# cyberspace-1-mainboard.net
KiCad netlist of a schematic drawn in EAGLE
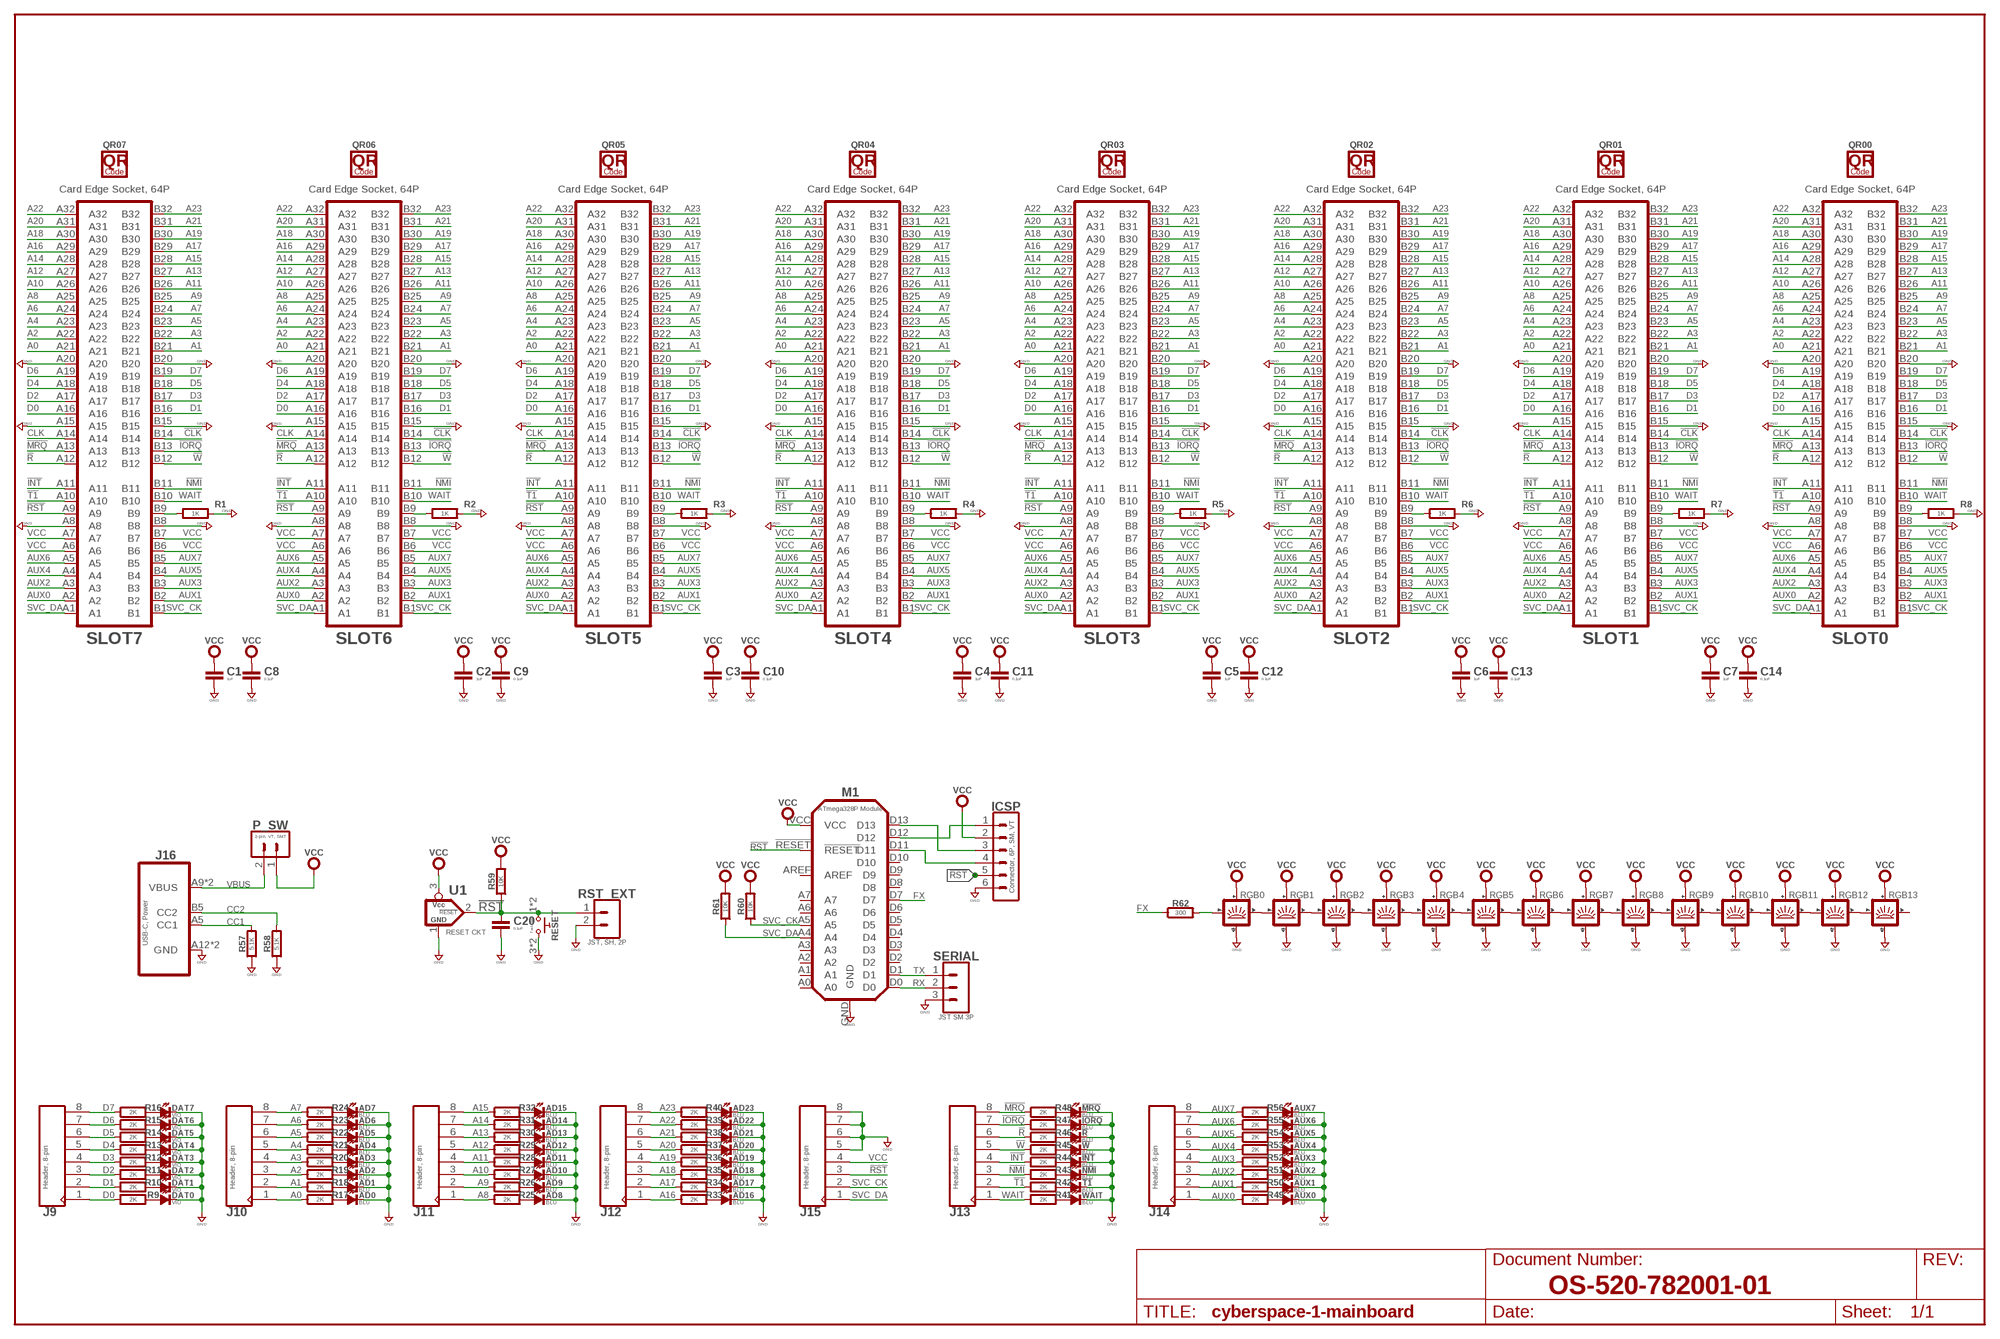
[diagram p0: schematic, sheet 1]

(export (version "E")
  (design (tool "Eeschema 10.0.6"))
  (components
    (comp (ref "!INT")
      (value "BLU")
      (footprint "eagle-import:SMD_0603")
      (libsource (lib "eagle-import") (part "SMT0603"))
    )
    (comp (ref "!IORQ")
      (value "BLU")
      (footprint "eagle-import:SMD_0603")
      (libsource (lib "eagle-import") (part "SMT0603"))
    )
    (comp (ref "!MRQ")
      (value "BLU")
      (footprint "eagle-import:SMD_0603")
      (libsource (lib "eagle-import") (part "SMT0603"))
    )
    (comp (ref "!NMI")
      (value "BLU")
      (footprint "eagle-import:SMD_0603")
      (libsource (lib "eagle-import") (part "SMT0603"))
    )
    (comp (ref "!R")
      (value "BLU")
      (footprint "eagle-import:SMD_0603")
      (libsource (lib "eagle-import") (part "SMT0603"))
    )
    (comp (ref "!T1")
      (value "BLU")
      (footprint "eagle-import:SMD_0603")
      (libsource (lib "eagle-import") (part "SMT0603"))
    )
    (comp (ref "!W")
      (value "BLU")
      (footprint "eagle-import:SMD_0603")
      (libsource (lib "eagle-import") (part "SMT0603"))
    )
    (comp (ref "AD0")
      (value "BLU")
      (footprint "eagle-import:SMD_0603")
      (libsource (lib "eagle-import") (part "SMT0603"))
    )
    (comp (ref "AD1")
      (value "BLU")
      (footprint "eagle-import:SMD_0603")
      (libsource (lib "eagle-import") (part "SMT0603"))
    )
    (comp (ref "AD2")
      (value "BLU")
      (footprint "eagle-import:SMD_0603")
      (libsource (lib "eagle-import") (part "SMT0603"))
    )
    (comp (ref "AD3")
      (value "BLU")
      (footprint "eagle-import:SMD_0603")
      (libsource (lib "eagle-import") (part "SMT0603"))
    )
    (comp (ref "AD4")
      (value "BLU")
      (footprint "eagle-import:SMD_0603")
      (libsource (lib "eagle-import") (part "SMT0603"))
    )
    (comp (ref "AD5")
      (value "BLU")
      (footprint "eagle-import:SMD_0603")
      (libsource (lib "eagle-import") (part "SMT0603"))
    )
    (comp (ref "AD6")
      (value "BLU")
      (footprint "eagle-import:SMD_0603")
      (libsource (lib "eagle-import") (part "SMT0603"))
    )
    (comp (ref "AD7")
      (value "BLU")
      (footprint "eagle-import:SMD_0603")
      (libsource (lib "eagle-import") (part "SMT0603"))
    )
    (comp (ref "AD8")
      (value "BLU")
      (footprint "eagle-import:SMD_0603")
      (libsource (lib "eagle-import") (part "SMT0603"))
    )
    (comp (ref "AD9")
      (value "BLU")
      (footprint "eagle-import:SMD_0603")
      (libsource (lib "eagle-import") (part "SMT0603"))
    )
    (comp (ref "AD10")
      (value "BLU")
      (footprint "eagle-import:SMD_0603")
      (libsource (lib "eagle-import") (part "SMT0603"))
    )
    (comp (ref "AD11")
      (value "BLU")
      (footprint "eagle-import:SMD_0603")
      (libsource (lib "eagle-import") (part "SMT0603"))
    )
    (comp (ref "AD12")
      (value "BLU")
      (footprint "eagle-import:SMD_0603")
      (libsource (lib "eagle-import") (part "SMT0603"))
    )
    (comp (ref "AD13")
      (value "BLU")
      (footprint "eagle-import:SMD_0603")
      (libsource (lib "eagle-import") (part "SMT0603"))
    )
    (comp (ref "AD14")
      (value "BLU")
      (footprint "eagle-import:SMD_0603")
      (libsource (lib "eagle-import") (part "SMT0603"))
    )
    (comp (ref "AD15")
      (value "BLU")
      (footprint "eagle-import:SMD_0603")
      (libsource (lib "eagle-import") (part "SMT0603"))
    )
    (comp (ref "AD16")
      (value "BLU")
      (footprint "eagle-import:SMD_0603")
      (libsource (lib "eagle-import") (part "SMT0603"))
    )
    (comp (ref "AD17")
      (value "BLU")
      (footprint "eagle-import:SMD_0603")
      (libsource (lib "eagle-import") (part "SMT0603"))
    )
    (comp (ref "AD18")
      (value "BLU")
      (footprint "eagle-import:SMD_0603")
      (libsource (lib "eagle-import") (part "SMT0603"))
    )
    (comp (ref "AD19")
      (value "BLU")
      (footprint "eagle-import:SMD_0603")
      (libsource (lib "eagle-import") (part "SMT0603"))
    )
    (comp (ref "AD20")
      (value "BLU")
      (footprint "eagle-import:SMD_0603")
      (libsource (lib "eagle-import") (part "SMT0603"))
    )
    (comp (ref "AD21")
      (value "BLU")
      (footprint "eagle-import:SMD_0603")
      (libsource (lib "eagle-import") (part "SMT0603"))
    )
    (comp (ref "AD22")
      (value "BLU")
      (footprint "eagle-import:SMD_0603")
      (libsource (lib "eagle-import") (part "SMT0603"))
    )
    (comp (ref "AD23")
      (value "BLU")
      (footprint "eagle-import:SMD_0603")
      (libsource (lib "eagle-import") (part "SMT0603"))
    )
    (comp (ref "AUX0")
      (value "BLU")
      (footprint "eagle-import:SMD_0603")
      (libsource (lib "eagle-import") (part "SMT0603"))
    )
    (comp (ref "AUX1")
      (value "BLU")
      (footprint "eagle-import:SMD_0603")
      (libsource (lib "eagle-import") (part "SMT0603"))
    )
    (comp (ref "AUX2")
      (value "BLU")
      (footprint "eagle-import:SMD_0603")
      (libsource (lib "eagle-import") (part "SMT0603"))
    )
    (comp (ref "AUX3")
      (value "BLU")
      (footprint "eagle-import:SMD_0603")
      (libsource (lib "eagle-import") (part "SMT0603"))
    )
    (comp (ref "AUX4")
      (value "BLU")
      (footprint "eagle-import:SMD_0603")
      (libsource (lib "eagle-import") (part "SMT0603"))
    )
    (comp (ref "AUX5")
      (value "BLU")
      (footprint "eagle-import:SMD_0603")
      (libsource (lib "eagle-import") (part "SMT0603"))
    )
    (comp (ref "AUX6")
      (value "BLU")
      (footprint "eagle-import:SMD_0603")
      (libsource (lib "eagle-import") (part "SMT0603"))
    )
    (comp (ref "AUX7")
      (value "BLU")
      (footprint "eagle-import:SMD_0603")
      (libsource (lib "eagle-import") (part "SMT0603"))
    )
    (comp (ref "C1")
      (value "1uF")
      (footprint "eagle-import:0603-CAP")
      (libsource (lib "eagle-import") (part "CAPACITOR0603"))
    )
    (comp (ref "C2")
      (value "1uF")
      (footprint "eagle-import:0603-CAP")
      (libsource (lib "eagle-import") (part "CAPACITOR0603"))
    )
    (comp (ref "C3")
      (value "1uF")
      (footprint "eagle-import:0603-CAP")
      (libsource (lib "eagle-import") (part "CAPACITOR0603"))
    )
    (comp (ref "C4")
      (value "1uF")
      (footprint "eagle-import:0603-CAP")
      (libsource (lib "eagle-import") (part "CAPACITOR0603"))
    )
    (comp (ref "C5")
      (value "1uF")
      (footprint "eagle-import:0603-CAP")
      (libsource (lib "eagle-import") (part "CAPACITOR0603"))
    )
    (comp (ref "C6")
      (value "1uF")
      (footprint "eagle-import:0603-CAP")
      (libsource (lib "eagle-import") (part "CAPACITOR0603"))
    )
    (comp (ref "C7")
      (value "1uF")
      (footprint "eagle-import:0603-CAP")
      (libsource (lib "eagle-import") (part "CAPACITOR0603"))
    )
    (comp (ref "C8")
      (value "0.1uF")
      (footprint "eagle-import:0603-CAP")
      (libsource (lib "eagle-import") (part "CAPACITOR0603"))
    )
    (comp (ref "C9")
      (value "0.1uF")
      (footprint "eagle-import:0603-CAP")
      (libsource (lib "eagle-import") (part "CAPACITOR0603"))
    )
    (comp (ref "C10")
      (value "0.1uF")
      (footprint "eagle-import:0603-CAP")
      (libsource (lib "eagle-import") (part "CAPACITOR0603"))
    )
    (comp (ref "C11")
      (value "0.1uF")
      (footprint "eagle-import:0603-CAP")
      (libsource (lib "eagle-import") (part "CAPACITOR0603"))
    )
    (comp (ref "C12")
      (value "0.1uF")
      (footprint "eagle-import:0603-CAP")
      (libsource (lib "eagle-import") (part "CAPACITOR0603"))
    )
    (comp (ref "C13")
      (value "0.1uF")
      (footprint "eagle-import:0603-CAP")
      (libsource (lib "eagle-import") (part "CAPACITOR0603"))
    )
    (comp (ref "C14")
      (value "0.1uF")
      (footprint "eagle-import:0603-CAP")
      (libsource (lib "eagle-import") (part "CAPACITOR0603"))
    )
    (comp (ref "C20")
      (value "0.1uF")
      (footprint "eagle-import:0603-CAP")
      (libsource (lib "eagle-import") (part "CAPACITOR0603"))
    )
    (comp (ref "DAT0")
      (value "VIO")
      (footprint "eagle-import:SMD_0603")
      (libsource (lib "eagle-import") (part "SMT0603"))
    )
    (comp (ref "DAT1")
      (value "VIO")
      (footprint "eagle-import:SMD_0603")
      (libsource (lib "eagle-import") (part "SMT0603"))
    )
    (comp (ref "DAT2")
      (value "VIO")
      (footprint "eagle-import:SMD_0603")
      (libsource (lib "eagle-import") (part "SMT0603"))
    )
    (comp (ref "DAT3")
      (value "VIO")
      (footprint "eagle-import:SMD_0603")
      (libsource (lib "eagle-import") (part "SMT0603"))
    )
    (comp (ref "DAT4")
      (value "VIO")
      (footprint "eagle-import:SMD_0603")
      (libsource (lib "eagle-import") (part "SMT0603"))
    )
    (comp (ref "DAT5")
      (value "VIO")
      (footprint "eagle-import:SMD_0603")
      (libsource (lib "eagle-import") (part "SMT0603"))
    )
    (comp (ref "DAT6")
      (value "VIO")
      (footprint "eagle-import:SMD_0603")
      (libsource (lib "eagle-import") (part "SMT0603"))
    )
    (comp (ref "DAT7")
      (value "VIO")
      (footprint "eagle-import:SMD_0603")
      (libsource (lib "eagle-import") (part "SMT0603"))
    )
    (comp (ref "ICSP")
      (value "Connector, 6P, SM, VT")
      (footprint "eagle-import:BM06B-SRSS-TB")
      (fields (field (name "MFR") "JST") (field (name "MPN") "BM06-SRSS-TB"))
      (libsource (lib "eagle-import") (part "06P-SM-VT-SMT"))
    )
    (comp (ref "J9")
      (value "Header, 8-pin")
      (footprint "eagle-import:MA08X1-VT-THD")
      (libsource (lib "eagle-import") (part "CON_08X1-VT-THD"))
    )
    (comp (ref "J10")
      (value "Header, 8-pin")
      (footprint "eagle-import:MA08X1-VT-THD")
      (libsource (lib "eagle-import") (part "CON_08X1-VT-THD"))
    )
    (comp (ref "J11")
      (value "Header, 8-pin")
      (footprint "eagle-import:MA08X1-VT-THD")
      (libsource (lib "eagle-import") (part "CON_08X1-VT-THD"))
    )
    (comp (ref "J12")
      (value "Header, 8-pin")
      (footprint "eagle-import:MA08X1-VT-THD")
      (libsource (lib "eagle-import") (part "CON_08X1-VT-THD"))
    )
    (comp (ref "J13")
      (value "Header, 8-pin")
      (footprint "eagle-import:MA08X1-VT-THD")
      (libsource (lib "eagle-import") (part "CON_08X1-VT-THD"))
    )
    (comp (ref "J14")
      (value "Header, 8-pin")
      (footprint "eagle-import:MA08X1-VT-THD")
      (libsource (lib "eagle-import") (part "CON_08X1-VT-THD"))
    )
    (comp (ref "J15")
      (value "Header, 8-pin")
      (footprint "eagle-import:MA08X1-VT-THD")
      (libsource (lib "eagle-import") (part "CON_08X1-VT-THD"))
    )
    (comp (ref "J16")
      (value "USB-C, Power")
      (footprint "eagle-import:GCT-USB4125")
      (fields (field (name "MFR") "GCT") (field (name "MPN") "USB4125"))
      (libsource (lib "eagle-import") (part "USB-C-PWRSMT-HORIZ"))
    )
    (comp (ref "M1")
      (value "ATmega328P Module")
      (footprint "eagle-import:0119A")
      (fields (field (name "MFR") "Circuit Monkey") (field (name "MPN") "0119A"))
      (libsource (lib "eagle-import") (part "0119REV-A"))
    )
    (comp (ref "P_SW")
      (value "2-pin, VT, SMT")
      (footprint "eagle-import:B2B-PH-SM4")
      (fields (field (name "MFR") "JST") (field (name "MPN") "B2B-PH-SM4"))
      (libsource (lib "eagle-import") (part "02PVT-SMT"))
    )
    (comp (ref "QR00")
      (value "QR_CODE-00-7MM")
      (footprint "eagle-import:QR-7MM-00")
      (libsource (lib "eagle-import") (part "QR_CODE-00-7MM"))
    )
    (comp (ref "QR01")
      (value "QR_CODE-01-7MM")
      (footprint "eagle-import:QR-7MM-01")
      (libsource (lib "eagle-import") (part "QR_CODE-01-7MM"))
    )
    (comp (ref "QR02")
      (value "QR_CODE-02-7MM")
      (footprint "eagle-import:QR-7MM-02")
      (libsource (lib "eagle-import") (part "QR_CODE-02-7MM"))
    )
    (comp (ref "QR03")
      (value "QR_CODE-03-7MM")
      (footprint "eagle-import:QR-7MM-03")
      (libsource (lib "eagle-import") (part "QR_CODE-03-7MM"))
    )
    (comp (ref "QR04")
      (value "QR_CODE-04-7MM")
      (footprint "eagle-import:QR-7MM-04")
      (libsource (lib "eagle-import") (part "QR_CODE-04-7MM"))
    )
    (comp (ref "QR05")
      (value "QR_CODE-05-7MM")
      (footprint "eagle-import:QR-7MM-05")
      (libsource (lib "eagle-import") (part "QR_CODE-05-7MM"))
    )
    (comp (ref "QR06")
      (value "QR_CODE-06-7MM")
      (footprint "eagle-import:QR-7MM-06")
      (libsource (lib "eagle-import") (part "QR_CODE-06-7MM"))
    )
    (comp (ref "QR07")
      (value "QR_CODE-07-7MM")
      (footprint "eagle-import:QR-7MM-07")
      (libsource (lib "eagle-import") (part "QR_CODE-07-7MM"))
    )
    (comp (ref "R1")
      (value "1K")
      (footprint "eagle-import:0603-RES")
      (libsource (lib "eagle-import") (part "RESISTOR0603"))
    )
    (comp (ref "R2")
      (value "1K")
      (footprint "eagle-import:0603-RES")
      (libsource (lib "eagle-import") (part "RESISTOR0603"))
    )
    (comp (ref "R3")
      (value "1K")
      (footprint "eagle-import:0603-RES")
      (libsource (lib "eagle-import") (part "RESISTOR0603"))
    )
    (comp (ref "R4")
      (value "1K")
      (footprint "eagle-import:0603-RES")
      (libsource (lib "eagle-import") (part "RESISTOR0603"))
    )
    (comp (ref "R5")
      (value "1K")
      (footprint "eagle-import:0603-RES")
      (libsource (lib "eagle-import") (part "RESISTOR0603"))
    )
    (comp (ref "R6")
      (value "1K")
      (footprint "eagle-import:0603-RES")
      (libsource (lib "eagle-import") (part "RESISTOR0603"))
    )
    (comp (ref "R7")
      (value "1K")
      (footprint "eagle-import:0603-RES")
      (libsource (lib "eagle-import") (part "RESISTOR0603"))
    )
    (comp (ref "R8")
      (value "1K")
      (footprint "eagle-import:0603-RES")
      (libsource (lib "eagle-import") (part "RESISTOR0603"))
    )
    (comp (ref "R9")
      (value "2K")
      (footprint "eagle-import:0603-RES")
      (libsource (lib "eagle-import") (part "RESISTOR0603"))
    )
    (comp (ref "R10")
      (value "2K")
      (footprint "eagle-import:0603-RES")
      (libsource (lib "eagle-import") (part "RESISTOR0603"))
    )
    (comp (ref "R11")
      (value "2K")
      (footprint "eagle-import:0603-RES")
      (libsource (lib "eagle-import") (part "RESISTOR0603"))
    )
    (comp (ref "R12")
      (value "2K")
      (footprint "eagle-import:0603-RES")
      (libsource (lib "eagle-import") (part "RESISTOR0603"))
    )
    (comp (ref "R13")
      (value "2K")
      (footprint "eagle-import:0603-RES")
      (libsource (lib "eagle-import") (part "RESISTOR0603"))
    )
    (comp (ref "R14")
      (value "2K")
      (footprint "eagle-import:0603-RES")
      (libsource (lib "eagle-import") (part "RESISTOR0603"))
    )
    (comp (ref "R15")
      (value "2K")
      (footprint "eagle-import:0603-RES")
      (libsource (lib "eagle-import") (part "RESISTOR0603"))
    )
    (comp (ref "R16")
      (value "2K")
      (footprint "eagle-import:0603-RES")
      (libsource (lib "eagle-import") (part "RESISTOR0603"))
    )
    (comp (ref "R17")
      (value "2K")
      (footprint "eagle-import:0603-RES")
      (libsource (lib "eagle-import") (part "RESISTOR0603"))
    )
    (comp (ref "R18")
      (value "2K")
      (footprint "eagle-import:0603-RES")
      (libsource (lib "eagle-import") (part "RESISTOR0603"))
    )
    (comp (ref "R19")
      (value "2K")
      (footprint "eagle-import:0603-RES")
      (libsource (lib "eagle-import") (part "RESISTOR0603"))
    )
    (comp (ref "R20")
      (value "2K")
      (footprint "eagle-import:0603-RES")
      (libsource (lib "eagle-import") (part "RESISTOR0603"))
    )
    (comp (ref "R21")
      (value "2K")
      (footprint "eagle-import:0603-RES")
      (libsource (lib "eagle-import") (part "RESISTOR0603"))
    )
    (comp (ref "R22")
      (value "2K")
      (footprint "eagle-import:0603-RES")
      (libsource (lib "eagle-import") (part "RESISTOR0603"))
    )
    (comp (ref "R23")
      (value "2K")
      (footprint "eagle-import:0603-RES")
      (libsource (lib "eagle-import") (part "RESISTOR0603"))
    )
    (comp (ref "R24")
      (value "2K")
      (footprint "eagle-import:0603-RES")
      (libsource (lib "eagle-import") (part "RESISTOR0603"))
    )
    (comp (ref "R25")
      (value "2K")
      (footprint "eagle-import:0603-RES")
      (libsource (lib "eagle-import") (part "RESISTOR0603"))
    )
    (comp (ref "R26")
      (value "2K")
      (footprint "eagle-import:0603-RES")
      (libsource (lib "eagle-import") (part "RESISTOR0603"))
    )
    (comp (ref "R27")
      (value "2K")
      (footprint "eagle-import:0603-RES")
      (libsource (lib "eagle-import") (part "RESISTOR0603"))
    )
    (comp (ref "R28")
      (value "2K")
      (footprint "eagle-import:0603-RES")
      (libsource (lib "eagle-import") (part "RESISTOR0603"))
    )
    (comp (ref "R29")
      (value "2K")
      (footprint "eagle-import:0603-RES")
      (libsource (lib "eagle-import") (part "RESISTOR0603"))
    )
    (comp (ref "R30")
      (value "2K")
      (footprint "eagle-import:0603-RES")
      (libsource (lib "eagle-import") (part "RESISTOR0603"))
    )
    (comp (ref "R31")
      (value "2K")
      (footprint "eagle-import:0603-RES")
      (libsource (lib "eagle-import") (part "RESISTOR0603"))
    )
    (comp (ref "R32")
      (value "2K")
      (footprint "eagle-import:0603-RES")
      (libsource (lib "eagle-import") (part "RESISTOR0603"))
    )
    (comp (ref "R33")
      (value "2K")
      (footprint "eagle-import:0603-RES")
      (libsource (lib "eagle-import") (part "RESISTOR0603"))
    )
    (comp (ref "R34")
      (value "2K")
      (footprint "eagle-import:0603-RES")
      (libsource (lib "eagle-import") (part "RESISTOR0603"))
    )
    (comp (ref "R35")
      (value "2K")
      (footprint "eagle-import:0603-RES")
      (libsource (lib "eagle-import") (part "RESISTOR0603"))
    )
    (comp (ref "R36")
      (value "2K")
      (footprint "eagle-import:0603-RES")
      (libsource (lib "eagle-import") (part "RESISTOR0603"))
    )
    (comp (ref "R37")
      (value "2K")
      (footprint "eagle-import:0603-RES")
      (libsource (lib "eagle-import") (part "RESISTOR0603"))
    )
    (comp (ref "R38")
      (value "2K")
      (footprint "eagle-import:0603-RES")
      (libsource (lib "eagle-import") (part "RESISTOR0603"))
    )
    (comp (ref "R39")
      (value "2K")
      (footprint "eagle-import:0603-RES")
      (libsource (lib "eagle-import") (part "RESISTOR0603"))
    )
    (comp (ref "R40")
      (value "2K")
      (footprint "eagle-import:0603-RES")
      (libsource (lib "eagle-import") (part "RESISTOR0603"))
    )
    (comp (ref "R41")
      (value "2K")
      (footprint "eagle-import:0603-RES")
      (libsource (lib "eagle-import") (part "RESISTOR0603"))
    )
    (comp (ref "R42")
      (value "2K")
      (footprint "eagle-import:0603-RES")
      (libsource (lib "eagle-import") (part "RESISTOR0603"))
    )
    (comp (ref "R43")
      (value "2K")
      (footprint "eagle-import:0603-RES")
      (libsource (lib "eagle-import") (part "RESISTOR0603"))
    )
    (comp (ref "R44")
      (value "2K")
      (footprint "eagle-import:0603-RES")
      (libsource (lib "eagle-import") (part "RESISTOR0603"))
    )
    (comp (ref "R45")
      (value "2K")
      (footprint "eagle-import:0603-RES")
      (libsource (lib "eagle-import") (part "RESISTOR0603"))
    )
    (comp (ref "R46")
      (value "2K")
      (footprint "eagle-import:0603-RES")
      (libsource (lib "eagle-import") (part "RESISTOR0603"))
    )
    (comp (ref "R47")
      (value "2K")
      (footprint "eagle-import:0603-RES")
      (libsource (lib "eagle-import") (part "RESISTOR0603"))
    )
    (comp (ref "R48")
      (value "2K")
      (footprint "eagle-import:0603-RES")
      (libsource (lib "eagle-import") (part "RESISTOR0603"))
    )
    (comp (ref "R49")
      (value "2K")
      (footprint "eagle-import:0603-RES")
      (libsource (lib "eagle-import") (part "RESISTOR0603"))
    )
    (comp (ref "R50")
      (value "2K")
      (footprint "eagle-import:0603-RES")
      (libsource (lib "eagle-import") (part "RESISTOR0603"))
    )
    (comp (ref "R51")
      (value "2K")
      (footprint "eagle-import:0603-RES")
      (libsource (lib "eagle-import") (part "RESISTOR0603"))
    )
    (comp (ref "R52")
      (value "2K")
      (footprint "eagle-import:0603-RES")
      (libsource (lib "eagle-import") (part "RESISTOR0603"))
    )
    (comp (ref "R53")
      (value "2K")
      (footprint "eagle-import:0603-RES")
      (libsource (lib "eagle-import") (part "RESISTOR0603"))
    )
    (comp (ref "R54")
      (value "2K")
      (footprint "eagle-import:0603-RES")
      (libsource (lib "eagle-import") (part "RESISTOR0603"))
    )
    (comp (ref "R55")
      (value "2K")
      (footprint "eagle-import:0603-RES")
      (libsource (lib "eagle-import") (part "RESISTOR0603"))
    )
    (comp (ref "R56")
      (value "2K")
      (footprint "eagle-import:0603-RES")
      (libsource (lib "eagle-import") (part "RESISTOR0603"))
    )
    (comp (ref "R57")
      (value "5.1K")
      (footprint "eagle-import:0603-RES")
      (libsource (lib "eagle-import") (part "RESISTOR0603"))
    )
    (comp (ref "R58")
      (value "5.1K")
      (footprint "eagle-import:0603-RES")
      (libsource (lib "eagle-import") (part "RESISTOR0603"))
    )
    (comp (ref "R59")
      (value "10K")
      (footprint "eagle-import:0603-RES")
      (libsource (lib "eagle-import") (part "RESISTOR0603"))
    )
    (comp (ref "R60")
      (value "10K")
      (footprint "eagle-import:0603-RES")
      (libsource (lib "eagle-import") (part "RESISTOR0603"))
    )
    (comp (ref "R61")
      (value "10K")
      (footprint "eagle-import:0603-RES")
      (libsource (lib "eagle-import") (part "RESISTOR0603"))
    )
    (comp (ref "R62")
      (value "300")
      (footprint "eagle-import:0603-RES")
      (libsource (lib "eagle-import") (part "RESISTOR0603"))
    )
    (comp (ref "RESET")
      (value "Tact. Sw.")
      (footprint "eagle-import:B3FS")
      (fields (field (name "MFR") "Omron") (field (name "MPN") "B3FS-10*"))
      (libsource (lib "eagle-import") (part "PUSHBTN-MOMB3FS"))
    )
    (comp (ref "RGB0")
      (value "SMART_LED4020-SIDE")
      (footprint "eagle-import:SMD_4020")
      (libsource (lib "eagle-import") (part "SMART_LED4020-SIDE"))
    )
    (comp (ref "RGB1")
      (value "SMART_LED4020-SIDE")
      (footprint "eagle-import:SMD_4020")
      (libsource (lib "eagle-import") (part "SMART_LED4020-SIDE"))
    )
    (comp (ref "RGB2")
      (value "SMART_LED4020-SIDE")
      (footprint "eagle-import:SMD_4020")
      (libsource (lib "eagle-import") (part "SMART_LED4020-SIDE"))
    )
    (comp (ref "RGB3")
      (value "SMART_LED4020-SIDE")
      (footprint "eagle-import:SMD_4020")
      (libsource (lib "eagle-import") (part "SMART_LED4020-SIDE"))
    )
    (comp (ref "RGB4")
      (value "SMART_LED4020-SIDE")
      (footprint "eagle-import:SMD_4020")
      (libsource (lib "eagle-import") (part "SMART_LED4020-SIDE"))
    )
    (comp (ref "RGB5")
      (value "SMART_LED4020-SIDE")
      (footprint "eagle-import:SMD_4020")
      (libsource (lib "eagle-import") (part "SMART_LED4020-SIDE"))
    )
    (comp (ref "RGB6")
      (value "SMART_LED4020-SIDE")
      (footprint "eagle-import:SMD_4020")
      (libsource (lib "eagle-import") (part "SMART_LED4020-SIDE"))
    )
    (comp (ref "RGB7")
      (value "SMART_LED4020-SIDE")
      (footprint "eagle-import:SMD_4020")
      (libsource (lib "eagle-import") (part "SMART_LED4020-SIDE"))
    )
    (comp (ref "RGB8")
      (value "SMART_LED4020-SIDE")
      (footprint "eagle-import:SMD_4020")
      (libsource (lib "eagle-import") (part "SMART_LED4020-SIDE"))
    )
    (comp (ref "RGB9")
      (value "SMART_LED4020-SIDE")
      (footprint "eagle-import:SMD_4020")
      (libsource (lib "eagle-import") (part "SMART_LED4020-SIDE"))
    )
    (comp (ref "RGB10")
      (value "SMART_LED4020-SIDE")
      (footprint "eagle-import:SMD_4020")
      (libsource (lib "eagle-import") (part "SMART_LED4020-SIDE"))
    )
    (comp (ref "RGB11")
      (value "SMART_LED4020-SIDE")
      (footprint "eagle-import:SMD_4020")
      (libsource (lib "eagle-import") (part "SMART_LED4020-SIDE"))
    )
    (comp (ref "RGB12")
      (value "SMART_LED4020-SIDE")
      (footprint "eagle-import:SMD_4020")
      (libsource (lib "eagle-import") (part "SMART_LED4020-SIDE"))
    )
    (comp (ref "RGB13")
      (value "SMART_LED4020-SIDE")
      (footprint "eagle-import:SMD_4020")
      (libsource (lib "eagle-import") (part "SMART_LED4020-SIDE"))
    )
    (comp (ref "RST_EXT")
      (value "JST, SH, 2P")
      (footprint "eagle-import:BM02B-SRSS-TB")
      (fields (field (name "MFR") "JST") (field (name "MPN") "BMB02B-SRSS-TB"))
      (libsource (lib "eagle-import") (part "02P-SM-VT-SMT"))
    )
    (comp (ref "SERIAL")
      (value "JST SM 3P")
      (footprint "eagle-import:BM03B-SRSS-TB")
      (fields (field (name "MFR") "JST") (field (name "MPN") "BM03B-SRSS-TB"))
      (libsource (lib "eagle-import") (part "03P-SM-VT-SMT"))
    )
    (comp (ref "SLOT0")
      (value "Card Edge Socket, 64P")
      (footprint "eagle-import:PCIE-64P-SOCKET")
      (fields (field (name "MFR") "FCI") (field (name "MPN") "10018784-xxx01"))
      (libsource (lib "eagle-import") (part "PCIE-64-SOCKET"))
    )
    (comp (ref "SLOT1")
      (value "Card Edge Socket, 64P")
      (footprint "eagle-import:PCIE-64P-SOCKET")
      (fields (field (name "MFR") "FCI") (field (name "MPN") "10018784-xxx01"))
      (libsource (lib "eagle-import") (part "PCIE-64-SOCKET"))
    )
    (comp (ref "SLOT2")
      (value "Card Edge Socket, 64P")
      (footprint "eagle-import:PCIE-64P-SOCKET")
      (fields (field (name "MFR") "FCI") (field (name "MPN") "10018784-xxx01"))
      (libsource (lib "eagle-import") (part "PCIE-64-SOCKET"))
    )
    (comp (ref "SLOT3")
      (value "Card Edge Socket, 64P")
      (footprint "eagle-import:PCIE-64P-SOCKET")
      (fields (field (name "MFR") "FCI") (field (name "MPN") "10018784-xxx01"))
      (libsource (lib "eagle-import") (part "PCIE-64-SOCKET"))
    )
    (comp (ref "SLOT4")
      (value "Card Edge Socket, 64P")
      (footprint "eagle-import:PCIE-64P-SOCKET")
      (fields (field (name "MFR") "FCI") (field (name "MPN") "10018784-xxx01"))
      (libsource (lib "eagle-import") (part "PCIE-64-SOCKET"))
    )
    (comp (ref "SLOT5")
      (value "Card Edge Socket, 64P")
      (footprint "eagle-import:PCIE-64P-SOCKET")
      (fields (field (name "MFR") "FCI") (field (name "MPN") "10018784-xxx01"))
      (libsource (lib "eagle-import") (part "PCIE-64-SOCKET"))
    )
    (comp (ref "SLOT6")
      (value "Card Edge Socket, 64P")
      (footprint "eagle-import:PCIE-64P-SOCKET")
      (fields (field (name "MFR") "FCI") (field (name "MPN") "10018784-xxx01"))
      (libsource (lib "eagle-import") (part "PCIE-64-SOCKET"))
    )
    (comp (ref "SLOT7")
      (value "Card Edge Socket, 64P")
      (footprint "eagle-import:PCIE-64P-SOCKET")
      (fields (field (name "MFR") "FCI") (field (name "MPN") "10018784-xxx01"))
      (libsource (lib "eagle-import") (part "PCIE-64-SOCKET"))
    )
    (comp (ref "U1")
      (value "RESET CKT")
      (footprint "eagle-import:SOT-23")
      (fields (field (name "MFR") "Diodes Inc.") (field (name "MPN") "APX803L40-47SA"))
      (libsource (lib "eagle-import") (part "RESET_CIRCUITAPX803S-SA"))
    )
    (comp (ref "WAIT")
      (value "BLU")
      (footprint "eagle-import:SMD_0603")
      (libsource (lib "eagle-import") (part "SMT0603"))
    )
  )
  (nets
    (net (code "1") (name "/A0") (class "Default")
      (node (ref "J10") (pin "1") (pinfunction "1_1") (pintype "passive"))
      (node (ref "R17") (pin "1") (pinfunction "1_1") (pintype "passive"))
      (node (ref "SLOT0") (pin "A21") (pinfunction "A21_A21") (pintype "bidirectional"))
      (node (ref "SLOT1") (pin "A21") (pinfunction "A21_A21") (pintype "bidirectional"))
      (node (ref "SLOT2") (pin "A21") (pinfunction "A21_A21") (pintype "bidirectional"))
      (node (ref "SLOT3") (pin "A21") (pinfunction "A21_A21") (pintype "bidirectional"))
      (node (ref "SLOT4") (pin "A21") (pinfunction "A21_A21") (pintype "bidirectional"))
      (node (ref "SLOT5") (pin "A21") (pinfunction "A21_A21") (pintype "bidirectional"))
      (node (ref "SLOT6") (pin "A21") (pinfunction "A21_A21") (pintype "bidirectional"))
      (node (ref "SLOT7") (pin "A21") (pinfunction "A21_A21") (pintype "bidirectional"))
    )
    (net (code "2") (name "/A1") (class "Default")
      (node (ref "J10") (pin "2") (pinfunction "2_2") (pintype "passive"))
      (node (ref "R18") (pin "1") (pinfunction "1_1") (pintype "passive"))
      (node (ref "SLOT0") (pin "B21") (pinfunction "B21_B21") (pintype "bidirectional"))
      (node (ref "SLOT1") (pin "B21") (pinfunction "B21_B21") (pintype "bidirectional"))
      (node (ref "SLOT2") (pin "B21") (pinfunction "B21_B21") (pintype "bidirectional"))
      (node (ref "SLOT3") (pin "B21") (pinfunction "B21_B21") (pintype "bidirectional"))
      (node (ref "SLOT4") (pin "B21") (pinfunction "B21_B21") (pintype "bidirectional"))
      (node (ref "SLOT5") (pin "B21") (pinfunction "B21_B21") (pintype "bidirectional"))
      (node (ref "SLOT6") (pin "B21") (pinfunction "B21_B21") (pintype "bidirectional"))
      (node (ref "SLOT7") (pin "B21") (pinfunction "B21_B21") (pintype "bidirectional"))
    )
    (net (code "3") (name "/A2") (class "Default")
      (node (ref "J10") (pin "3") (pinfunction "3_3") (pintype "passive"))
      (node (ref "R19") (pin "1") (pinfunction "1_1") (pintype "passive"))
      (node (ref "SLOT0") (pin "A22") (pinfunction "A22_A22") (pintype "bidirectional"))
      (node (ref "SLOT1") (pin "A22") (pinfunction "A22_A22") (pintype "bidirectional"))
      (node (ref "SLOT2") (pin "A22") (pinfunction "A22_A22") (pintype "bidirectional"))
      (node (ref "SLOT3") (pin "A22") (pinfunction "A22_A22") (pintype "bidirectional"))
      (node (ref "SLOT4") (pin "A22") (pinfunction "A22_A22") (pintype "bidirectional"))
      (node (ref "SLOT5") (pin "A22") (pinfunction "A22_A22") (pintype "bidirectional"))
      (node (ref "SLOT6") (pin "A22") (pinfunction "A22_A22") (pintype "bidirectional"))
      (node (ref "SLOT7") (pin "A22") (pinfunction "A22_A22") (pintype "bidirectional"))
    )
    (net (code "4") (name "/A3") (class "Default")
      (node (ref "J10") (pin "4") (pinfunction "4_4") (pintype "passive"))
      (node (ref "R20") (pin "1") (pinfunction "1_1") (pintype "passive"))
      (node (ref "SLOT0") (pin "B22") (pinfunction "B22_B22") (pintype "bidirectional"))
      (node (ref "SLOT1") (pin "B22") (pinfunction "B22_B22") (pintype "bidirectional"))
      (node (ref "SLOT2") (pin "B22") (pinfunction "B22_B22") (pintype "bidirectional"))
      (node (ref "SLOT3") (pin "B22") (pinfunction "B22_B22") (pintype "bidirectional"))
      (node (ref "SLOT4") (pin "B22") (pinfunction "B22_B22") (pintype "bidirectional"))
      (node (ref "SLOT5") (pin "B22") (pinfunction "B22_B22") (pintype "bidirectional"))
      (node (ref "SLOT6") (pin "B22") (pinfunction "B22_B22") (pintype "bidirectional"))
      (node (ref "SLOT7") (pin "B22") (pinfunction "B22_B22") (pintype "bidirectional"))
    )
    (net (code "5") (name "/A4") (class "Default")
      (node (ref "J10") (pin "5") (pinfunction "5_5") (pintype "passive"))
      (node (ref "R21") (pin "1") (pinfunction "1_1") (pintype "passive"))
      (node (ref "SLOT0") (pin "A23") (pinfunction "A23_A23") (pintype "bidirectional"))
      (node (ref "SLOT1") (pin "A23") (pinfunction "A23_A23") (pintype "bidirectional"))
      (node (ref "SLOT2") (pin "A23") (pinfunction "A23_A23") (pintype "bidirectional"))
      (node (ref "SLOT3") (pin "A23") (pinfunction "A23_A23") (pintype "bidirectional"))
      (node (ref "SLOT4") (pin "A23") (pinfunction "A23_A23") (pintype "bidirectional"))
      (node (ref "SLOT5") (pin "A23") (pinfunction "A23_A23") (pintype "bidirectional"))
      (node (ref "SLOT6") (pin "A23") (pinfunction "A23_A23") (pintype "bidirectional"))
      (node (ref "SLOT7") (pin "A23") (pinfunction "A23_A23") (pintype "bidirectional"))
    )
    (net (code "6") (name "/A5") (class "Default")
      (node (ref "J10") (pin "6") (pinfunction "6_6") (pintype "passive"))
      (node (ref "R22") (pin "1") (pinfunction "1_1") (pintype "passive"))
      (node (ref "SLOT0") (pin "B23") (pinfunction "B23_B23") (pintype "bidirectional"))
      (node (ref "SLOT1") (pin "B23") (pinfunction "B23_B23") (pintype "bidirectional"))
      (node (ref "SLOT2") (pin "B23") (pinfunction "B23_B23") (pintype "bidirectional"))
      (node (ref "SLOT3") (pin "B23") (pinfunction "B23_B23") (pintype "bidirectional"))
      (node (ref "SLOT4") (pin "B23") (pinfunction "B23_B23") (pintype "bidirectional"))
      (node (ref "SLOT5") (pin "B23") (pinfunction "B23_B23") (pintype "bidirectional"))
      (node (ref "SLOT6") (pin "B23") (pinfunction "B23_B23") (pintype "bidirectional"))
      (node (ref "SLOT7") (pin "B23") (pinfunction "B23_B23") (pintype "bidirectional"))
    )
    (net (code "7") (name "/A6") (class "Default")
      (node (ref "J10") (pin "7") (pinfunction "7_7") (pintype "passive"))
      (node (ref "R23") (pin "1") (pinfunction "1_1") (pintype "passive"))
      (node (ref "SLOT0") (pin "A24") (pinfunction "A24_A24") (pintype "bidirectional"))
      (node (ref "SLOT1") (pin "A24") (pinfunction "A24_A24") (pintype "bidirectional"))
      (node (ref "SLOT2") (pin "A24") (pinfunction "A24_A24") (pintype "bidirectional"))
      (node (ref "SLOT3") (pin "A24") (pinfunction "A24_A24") (pintype "bidirectional"))
      (node (ref "SLOT4") (pin "A24") (pinfunction "A24_A24") (pintype "bidirectional"))
      (node (ref "SLOT5") (pin "A24") (pinfunction "A24_A24") (pintype "bidirectional"))
      (node (ref "SLOT6") (pin "A24") (pinfunction "A24_A24") (pintype "bidirectional"))
      (node (ref "SLOT7") (pin "A24") (pinfunction "A24_A24") (pintype "bidirectional"))
    )
    (net (code "8") (name "/A7") (class "Default")
      (node (ref "J10") (pin "8") (pinfunction "8_8") (pintype "passive"))
      (node (ref "R24") (pin "1") (pinfunction "1_1") (pintype "passive"))
      (node (ref "SLOT0") (pin "B24") (pinfunction "B24_B24") (pintype "bidirectional"))
      (node (ref "SLOT1") (pin "B24") (pinfunction "B24_B24") (pintype "bidirectional"))
      (node (ref "SLOT2") (pin "B24") (pinfunction "B24_B24") (pintype "bidirectional"))
      (node (ref "SLOT3") (pin "B24") (pinfunction "B24_B24") (pintype "bidirectional"))
      (node (ref "SLOT4") (pin "B24") (pinfunction "B24_B24") (pintype "bidirectional"))
      (node (ref "SLOT5") (pin "B24") (pinfunction "B24_B24") (pintype "bidirectional"))
      (node (ref "SLOT6") (pin "B24") (pinfunction "B24_B24") (pintype "bidirectional"))
      (node (ref "SLOT7") (pin "B24") (pinfunction "B24_B24") (pintype "bidirectional"))
    )
    (net (code "9") (name "/A8") (class "Default")
      (node (ref "J11") (pin "1") (pinfunction "1_1") (pintype "passive"))
      (node (ref "R25") (pin "1") (pinfunction "1_1") (pintype "passive"))
      (node (ref "SLOT0") (pin "A25") (pinfunction "A25_A25") (pintype "bidirectional"))
      (node (ref "SLOT1") (pin "A25") (pinfunction "A25_A25") (pintype "bidirectional"))
      (node (ref "SLOT2") (pin "A25") (pinfunction "A25_A25") (pintype "bidirectional"))
      (node (ref "SLOT3") (pin "A25") (pinfunction "A25_A25") (pintype "bidirectional"))
      (node (ref "SLOT4") (pin "A25") (pinfunction "A25_A25") (pintype "bidirectional"))
      (node (ref "SLOT5") (pin "A25") (pinfunction "A25_A25") (pintype "bidirectional"))
      (node (ref "SLOT6") (pin "A25") (pinfunction "A25_A25") (pintype "bidirectional"))
      (node (ref "SLOT7") (pin "A25") (pinfunction "A25_A25") (pintype "bidirectional"))
    )
    (net (code "10") (name "/A9") (class "Default")
      (node (ref "J11") (pin "2") (pinfunction "2_2") (pintype "passive"))
      (node (ref "R26") (pin "1") (pinfunction "1_1") (pintype "passive"))
      (node (ref "SLOT0") (pin "B25") (pinfunction "B25_B25") (pintype "bidirectional"))
      (node (ref "SLOT1") (pin "B25") (pinfunction "B25_B25") (pintype "bidirectional"))
      (node (ref "SLOT2") (pin "B25") (pinfunction "B25_B25") (pintype "bidirectional"))
      (node (ref "SLOT3") (pin "B25") (pinfunction "B25_B25") (pintype "bidirectional"))
      (node (ref "SLOT4") (pin "B25") (pinfunction "B25_B25") (pintype "bidirectional"))
      (node (ref "SLOT5") (pin "B25") (pinfunction "B25_B25") (pintype "bidirectional"))
      (node (ref "SLOT6") (pin "B25") (pinfunction "B25_B25") (pintype "bidirectional"))
      (node (ref "SLOT7") (pin "B25") (pinfunction "B25_B25") (pintype "bidirectional"))
    )
    (net (code "11") (name "/A10") (class "Default")
      (node (ref "J11") (pin "3") (pinfunction "3_3") (pintype "passive"))
      (node (ref "R27") (pin "1") (pinfunction "1_1") (pintype "passive"))
      (node (ref "SLOT0") (pin "A26") (pinfunction "A26_A26") (pintype "bidirectional"))
      (node (ref "SLOT1") (pin "A26") (pinfunction "A26_A26") (pintype "bidirectional"))
      (node (ref "SLOT2") (pin "A26") (pinfunction "A26_A26") (pintype "bidirectional"))
      (node (ref "SLOT3") (pin "A26") (pinfunction "A26_A26") (pintype "bidirectional"))
      (node (ref "SLOT4") (pin "A26") (pinfunction "A26_A26") (pintype "bidirectional"))
      (node (ref "SLOT5") (pin "A26") (pinfunction "A26_A26") (pintype "bidirectional"))
      (node (ref "SLOT6") (pin "A26") (pinfunction "A26_A26") (pintype "bidirectional"))
      (node (ref "SLOT7") (pin "A26") (pinfunction "A26_A26") (pintype "bidirectional"))
    )
    (net (code "12") (name "/A11") (class "Default")
      (node (ref "J11") (pin "4") (pinfunction "4_4") (pintype "passive"))
      (node (ref "R28") (pin "1") (pinfunction "1_1") (pintype "passive"))
      (node (ref "SLOT0") (pin "B26") (pinfunction "B26_B26") (pintype "bidirectional"))
      (node (ref "SLOT1") (pin "B26") (pinfunction "B26_B26") (pintype "bidirectional"))
      (node (ref "SLOT2") (pin "B26") (pinfunction "B26_B26") (pintype "bidirectional"))
      (node (ref "SLOT3") (pin "B26") (pinfunction "B26_B26") (pintype "bidirectional"))
      (node (ref "SLOT4") (pin "B26") (pinfunction "B26_B26") (pintype "bidirectional"))
      (node (ref "SLOT5") (pin "B26") (pinfunction "B26_B26") (pintype "bidirectional"))
      (node (ref "SLOT6") (pin "B26") (pinfunction "B26_B26") (pintype "bidirectional"))
      (node (ref "SLOT7") (pin "B26") (pinfunction "B26_B26") (pintype "bidirectional"))
    )
    (net (code "13") (name "/A12") (class "Default")
      (node (ref "J11") (pin "5") (pinfunction "5_5") (pintype "passive"))
      (node (ref "R29") (pin "1") (pinfunction "1_1") (pintype "passive"))
      (node (ref "SLOT0") (pin "A27") (pinfunction "A27_A27") (pintype "bidirectional"))
      (node (ref "SLOT1") (pin "A27") (pinfunction "A27_A27") (pintype "bidirectional"))
      (node (ref "SLOT2") (pin "A27") (pinfunction "A27_A27") (pintype "bidirectional"))
      (node (ref "SLOT3") (pin "A27") (pinfunction "A27_A27") (pintype "bidirectional"))
      (node (ref "SLOT4") (pin "A27") (pinfunction "A27_A27") (pintype "bidirectional"))
      (node (ref "SLOT5") (pin "A27") (pinfunction "A27_A27") (pintype "bidirectional"))
      (node (ref "SLOT6") (pin "A27") (pinfunction "A27_A27") (pintype "bidirectional"))
      (node (ref "SLOT7") (pin "A27") (pinfunction "A27_A27") (pintype "bidirectional"))
    )
    (net (code "14") (name "/A13") (class "Default")
      (node (ref "J11") (pin "6") (pinfunction "6_6") (pintype "passive"))
      (node (ref "R30") (pin "1") (pinfunction "1_1") (pintype "passive"))
      (node (ref "SLOT0") (pin "B27") (pinfunction "B27_B27") (pintype "bidirectional"))
      (node (ref "SLOT1") (pin "B27") (pinfunction "B27_B27") (pintype "bidirectional"))
      (node (ref "SLOT2") (pin "B27") (pinfunction "B27_B27") (pintype "bidirectional"))
      (node (ref "SLOT3") (pin "B27") (pinfunction "B27_B27") (pintype "bidirectional"))
      (node (ref "SLOT4") (pin "B27") (pinfunction "B27_B27") (pintype "bidirectional"))
      (node (ref "SLOT5") (pin "B27") (pinfunction "B27_B27") (pintype "bidirectional"))
      (node (ref "SLOT6") (pin "B27") (pinfunction "B27_B27") (pintype "bidirectional"))
      (node (ref "SLOT7") (pin "B27") (pinfunction "B27_B27") (pintype "bidirectional"))
    )
    (net (code "15") (name "/A14") (class "Default")
      (node (ref "J11") (pin "7") (pinfunction "7_7") (pintype "passive"))
      (node (ref "R31") (pin "1") (pinfunction "1_1") (pintype "passive"))
      (node (ref "SLOT0") (pin "A28") (pinfunction "A28_A28") (pintype "bidirectional"))
      (node (ref "SLOT1") (pin "A28") (pinfunction "A28_A28") (pintype "bidirectional"))
      (node (ref "SLOT2") (pin "A28") (pinfunction "A28_A28") (pintype "bidirectional"))
      (node (ref "SLOT3") (pin "A28") (pinfunction "A28_A28") (pintype "bidirectional"))
      (node (ref "SLOT4") (pin "A28") (pinfunction "A28_A28") (pintype "bidirectional"))
      (node (ref "SLOT5") (pin "A28") (pinfunction "A28_A28") (pintype "bidirectional"))
      (node (ref "SLOT6") (pin "A28") (pinfunction "A28_A28") (pintype "bidirectional"))
      (node (ref "SLOT7") (pin "A28") (pinfunction "A28_A28") (pintype "bidirectional"))
    )
    (net (code "16") (name "/A15") (class "Default")
      (node (ref "J11") (pin "8") (pinfunction "8_8") (pintype "passive"))
      (node (ref "R32") (pin "1") (pinfunction "1_1") (pintype "passive"))
      (node (ref "SLOT0") (pin "B28") (pinfunction "B28_B28") (pintype "bidirectional"))
      (node (ref "SLOT1") (pin "B28") (pinfunction "B28_B28") (pintype "bidirectional"))
      (node (ref "SLOT2") (pin "B28") (pinfunction "B28_B28") (pintype "bidirectional"))
      (node (ref "SLOT3") (pin "B28") (pinfunction "B28_B28") (pintype "bidirectional"))
      (node (ref "SLOT4") (pin "B28") (pinfunction "B28_B28") (pintype "bidirectional"))
      (node (ref "SLOT5") (pin "B28") (pinfunction "B28_B28") (pintype "bidirectional"))
      (node (ref "SLOT6") (pin "B28") (pinfunction "B28_B28") (pintype "bidirectional"))
      (node (ref "SLOT7") (pin "B28") (pinfunction "B28_B28") (pintype "bidirectional"))
    )
    (net (code "17") (name "/A16") (class "Default")
      (node (ref "J12") (pin "1") (pinfunction "1_1") (pintype "passive"))
      (node (ref "R33") (pin "1") (pinfunction "1_1") (pintype "passive"))
      (node (ref "SLOT0") (pin "A29") (pinfunction "A29_A29") (pintype "bidirectional"))
      (node (ref "SLOT1") (pin "A29") (pinfunction "A29_A29") (pintype "bidirectional"))
      (node (ref "SLOT2") (pin "A29") (pinfunction "A29_A29") (pintype "bidirectional"))
      (node (ref "SLOT3") (pin "A29") (pinfunction "A29_A29") (pintype "bidirectional"))
      (node (ref "SLOT4") (pin "A29") (pinfunction "A29_A29") (pintype "bidirectional"))
      (node (ref "SLOT5") (pin "A29") (pinfunction "A29_A29") (pintype "bidirectional"))
      (node (ref "SLOT6") (pin "A29") (pinfunction "A29_A29") (pintype "bidirectional"))
      (node (ref "SLOT7") (pin "A29") (pinfunction "A29_A29") (pintype "bidirectional"))
    )
    (net (code "18") (name "/A17") (class "Default")
      (node (ref "J12") (pin "2") (pinfunction "2_2") (pintype "passive"))
      (node (ref "R34") (pin "1") (pinfunction "1_1") (pintype "passive"))
      (node (ref "SLOT0") (pin "B29") (pinfunction "B29_B29") (pintype "bidirectional"))
      (node (ref "SLOT1") (pin "B29") (pinfunction "B29_B29") (pintype "bidirectional"))
      (node (ref "SLOT2") (pin "B29") (pinfunction "B29_B29") (pintype "bidirectional"))
      (node (ref "SLOT3") (pin "B29") (pinfunction "B29_B29") (pintype "bidirectional"))
      (node (ref "SLOT4") (pin "B29") (pinfunction "B29_B29") (pintype "bidirectional"))
      (node (ref "SLOT5") (pin "B29") (pinfunction "B29_B29") (pintype "bidirectional"))
      (node (ref "SLOT6") (pin "B29") (pinfunction "B29_B29") (pintype "bidirectional"))
      (node (ref "SLOT7") (pin "B29") (pinfunction "B29_B29") (pintype "bidirectional"))
    )
    (net (code "19") (name "/A18") (class "Default")
      (node (ref "J12") (pin "3") (pinfunction "3_3") (pintype "passive"))
      (node (ref "R35") (pin "1") (pinfunction "1_1") (pintype "passive"))
      (node (ref "SLOT0") (pin "A30") (pinfunction "A30_A30") (pintype "bidirectional"))
      (node (ref "SLOT1") (pin "A30") (pinfunction "A30_A30") (pintype "bidirectional"))
      (node (ref "SLOT2") (pin "A30") (pinfunction "A30_A30") (pintype "bidirectional"))
      (node (ref "SLOT3") (pin "A30") (pinfunction "A30_A30") (pintype "bidirectional"))
      (node (ref "SLOT4") (pin "A30") (pinfunction "A30_A30") (pintype "bidirectional"))
      (node (ref "SLOT5") (pin "A30") (pinfunction "A30_A30") (pintype "bidirectional"))
      (node (ref "SLOT6") (pin "A30") (pinfunction "A30_A30") (pintype "bidirectional"))
      (node (ref "SLOT7") (pin "A30") (pinfunction "A30_A30") (pintype "bidirectional"))
    )
    (net (code "20") (name "/A19") (class "Default")
      (node (ref "J12") (pin "4") (pinfunction "4_4") (pintype "passive"))
      (node (ref "R36") (pin "1") (pinfunction "1_1") (pintype "passive"))
      (node (ref "SLOT0") (pin "B30") (pinfunction "B30_B30") (pintype "bidirectional"))
      (node (ref "SLOT1") (pin "B30") (pinfunction "B30_B30") (pintype "bidirectional"))
      (node (ref "SLOT2") (pin "B30") (pinfunction "B30_B30") (pintype "bidirectional"))
      (node (ref "SLOT3") (pin "B30") (pinfunction "B30_B30") (pintype "bidirectional"))
      (node (ref "SLOT4") (pin "B30") (pinfunction "B30_B30") (pintype "bidirectional"))
      (node (ref "SLOT5") (pin "B30") (pinfunction "B30_B30") (pintype "bidirectional"))
      (node (ref "SLOT6") (pin "B30") (pinfunction "B30_B30") (pintype "bidirectional"))
      (node (ref "SLOT7") (pin "B30") (pinfunction "B30_B30") (pintype "bidirectional"))
    )
    (net (code "21") (name "/A20") (class "Default")
      (node (ref "J12") (pin "5") (pinfunction "5_5") (pintype "passive"))
      (node (ref "R37") (pin "1") (pinfunction "1_1") (pintype "passive"))
      (node (ref "SLOT0") (pin "A31") (pinfunction "A31_A31") (pintype "bidirectional"))
      (node (ref "SLOT1") (pin "A31") (pinfunction "A31_A31") (pintype "bidirectional"))
      (node (ref "SLOT2") (pin "A31") (pinfunction "A31_A31") (pintype "bidirectional"))
      (node (ref "SLOT3") (pin "A31") (pinfunction "A31_A31") (pintype "bidirectional"))
      (node (ref "SLOT4") (pin "A31") (pinfunction "A31_A31") (pintype "bidirectional"))
      (node (ref "SLOT5") (pin "A31") (pinfunction "A31_A31") (pintype "bidirectional"))
      (node (ref "SLOT6") (pin "A31") (pinfunction "A31_A31") (pintype "bidirectional"))
      (node (ref "SLOT7") (pin "A31") (pinfunction "A31_A31") (pintype "bidirectional"))
    )
    (net (code "22") (name "/A21") (class "Default")
      (node (ref "J12") (pin "6") (pinfunction "6_6") (pintype "passive"))
      (node (ref "R38") (pin "1") (pinfunction "1_1") (pintype "passive"))
      (node (ref "SLOT0") (pin "B31") (pinfunction "B31_B31") (pintype "bidirectional"))
      (node (ref "SLOT1") (pin "B31") (pinfunction "B31_B31") (pintype "bidirectional"))
      (node (ref "SLOT2") (pin "B31") (pinfunction "B31_B31") (pintype "bidirectional"))
      (node (ref "SLOT3") (pin "B31") (pinfunction "B31_B31") (pintype "bidirectional"))
      (node (ref "SLOT4") (pin "B31") (pinfunction "B31_B31") (pintype "bidirectional"))
      (node (ref "SLOT5") (pin "B31") (pinfunction "B31_B31") (pintype "bidirectional"))
      (node (ref "SLOT6") (pin "B31") (pinfunction "B31_B31") (pintype "bidirectional"))
      (node (ref "SLOT7") (pin "B31") (pinfunction "B31_B31") (pintype "bidirectional"))
    )
    (net (code "23") (name "/A22") (class "Default")
      (node (ref "J12") (pin "7") (pinfunction "7_7") (pintype "passive"))
      (node (ref "R39") (pin "1") (pinfunction "1_1") (pintype "passive"))
      (node (ref "SLOT0") (pin "A32") (pinfunction "A32_A32") (pintype "bidirectional"))
      (node (ref "SLOT1") (pin "A32") (pinfunction "A32_A32") (pintype "bidirectional"))
      (node (ref "SLOT2") (pin "A32") (pinfunction "A32_A32") (pintype "bidirectional"))
      (node (ref "SLOT3") (pin "A32") (pinfunction "A32_A32") (pintype "bidirectional"))
      (node (ref "SLOT4") (pin "A32") (pinfunction "A32_A32") (pintype "bidirectional"))
      (node (ref "SLOT5") (pin "A32") (pinfunction "A32_A32") (pintype "bidirectional"))
      (node (ref "SLOT6") (pin "A32") (pinfunction "A32_A32") (pintype "bidirectional"))
      (node (ref "SLOT7") (pin "A32") (pinfunction "A32_A32") (pintype "bidirectional"))
    )
    (net (code "24") (name "/A23") (class "Default")
      (node (ref "J12") (pin "8") (pinfunction "8_8") (pintype "passive"))
      (node (ref "R40") (pin "1") (pinfunction "1_1") (pintype "passive"))
      (node (ref "SLOT0") (pin "B32") (pinfunction "B32_B32") (pintype "bidirectional"))
      (node (ref "SLOT1") (pin "B32") (pinfunction "B32_B32") (pintype "bidirectional"))
      (node (ref "SLOT2") (pin "B32") (pinfunction "B32_B32") (pintype "bidirectional"))
      (node (ref "SLOT3") (pin "B32") (pinfunction "B32_B32") (pintype "bidirectional"))
      (node (ref "SLOT4") (pin "B32") (pinfunction "B32_B32") (pintype "bidirectional"))
      (node (ref "SLOT5") (pin "B32") (pinfunction "B32_B32") (pintype "bidirectional"))
      (node (ref "SLOT6") (pin "B32") (pinfunction "B32_B32") (pintype "bidirectional"))
      (node (ref "SLOT7") (pin "B32") (pinfunction "B32_B32") (pintype "bidirectional"))
    )
    (net (code "25") (name "/AUX0") (class "Default")
      (node (ref "J14") (pin "1") (pinfunction "1_1") (pintype "passive"))
      (node (ref "R49") (pin "1") (pinfunction "1_1") (pintype "passive"))
      (node (ref "SLOT0") (pin "A2") (pinfunction "A2_A2") (pintype "bidirectional"))
      (node (ref "SLOT1") (pin "A2") (pinfunction "A2_A2") (pintype "bidirectional"))
      (node (ref "SLOT2") (pin "A2") (pinfunction "A2_A2") (pintype "bidirectional"))
      (node (ref "SLOT3") (pin "A2") (pinfunction "A2_A2") (pintype "bidirectional"))
      (node (ref "SLOT4") (pin "A2") (pinfunction "A2_A2") (pintype "bidirectional"))
      (node (ref "SLOT5") (pin "A2") (pinfunction "A2_A2") (pintype "bidirectional"))
      (node (ref "SLOT6") (pin "A2") (pinfunction "A2_A2") (pintype "bidirectional"))
      (node (ref "SLOT7") (pin "A2") (pinfunction "A2_A2") (pintype "bidirectional"))
    )
    (net (code "26") (name "/AUX1") (class "Default")
      (node (ref "J14") (pin "2") (pinfunction "2_2") (pintype "passive"))
      (node (ref "R50") (pin "1") (pinfunction "1_1") (pintype "passive"))
      (node (ref "SLOT0") (pin "B2") (pinfunction "B2_B2") (pintype "bidirectional"))
      (node (ref "SLOT1") (pin "B2") (pinfunction "B2_B2") (pintype "bidirectional"))
      (node (ref "SLOT2") (pin "B2") (pinfunction "B2_B2") (pintype "bidirectional"))
      (node (ref "SLOT3") (pin "B2") (pinfunction "B2_B2") (pintype "bidirectional"))
      (node (ref "SLOT4") (pin "B2") (pinfunction "B2_B2") (pintype "bidirectional"))
      (node (ref "SLOT5") (pin "B2") (pinfunction "B2_B2") (pintype "bidirectional"))
      (node (ref "SLOT6") (pin "B2") (pinfunction "B2_B2") (pintype "bidirectional"))
      (node (ref "SLOT7") (pin "B2") (pinfunction "B2_B2") (pintype "bidirectional"))
    )
    (net (code "27") (name "/AUX2") (class "Default")
      (node (ref "J14") (pin "3") (pinfunction "3_3") (pintype "passive"))
      (node (ref "R51") (pin "1") (pinfunction "1_1") (pintype "passive"))
      (node (ref "SLOT0") (pin "A3") (pinfunction "A3_A3") (pintype "bidirectional"))
      (node (ref "SLOT1") (pin "A3") (pinfunction "A3_A3") (pintype "bidirectional"))
      (node (ref "SLOT2") (pin "A3") (pinfunction "A3_A3") (pintype "bidirectional"))
      (node (ref "SLOT3") (pin "A3") (pinfunction "A3_A3") (pintype "bidirectional"))
      (node (ref "SLOT4") (pin "A3") (pinfunction "A3_A3") (pintype "bidirectional"))
      (node (ref "SLOT5") (pin "A3") (pinfunction "A3_A3") (pintype "bidirectional"))
      (node (ref "SLOT6") (pin "A3") (pinfunction "A3_A3") (pintype "bidirectional"))
      (node (ref "SLOT7") (pin "A3") (pinfunction "A3_A3") (pintype "bidirectional"))
    )
    (net (code "28") (name "/AUX3") (class "Default")
      (node (ref "J14") (pin "4") (pinfunction "4_4") (pintype "passive"))
      (node (ref "R52") (pin "1") (pinfunction "1_1") (pintype "passive"))
      (node (ref "SLOT0") (pin "B3") (pinfunction "B3_B3") (pintype "bidirectional"))
      (node (ref "SLOT1") (pin "B3") (pinfunction "B3_B3") (pintype "bidirectional"))
      (node (ref "SLOT2") (pin "B3") (pinfunction "B3_B3") (pintype "bidirectional"))
      (node (ref "SLOT3") (pin "B3") (pinfunction "B3_B3") (pintype "bidirectional"))
      (node (ref "SLOT4") (pin "B3") (pinfunction "B3_B3") (pintype "bidirectional"))
      (node (ref "SLOT5") (pin "B3") (pinfunction "B3_B3") (pintype "bidirectional"))
      (node (ref "SLOT6") (pin "B3") (pinfunction "B3_B3") (pintype "bidirectional"))
      (node (ref "SLOT7") (pin "B3") (pinfunction "B3_B3") (pintype "bidirectional"))
    )
    (net (code "29") (name "/AUX4") (class "Default")
      (node (ref "J14") (pin "5") (pinfunction "5_5") (pintype "passive"))
      (node (ref "R53") (pin "1") (pinfunction "1_1") (pintype "passive"))
      (node (ref "SLOT0") (pin "A4") (pinfunction "A4_A4") (pintype "bidirectional"))
      (node (ref "SLOT1") (pin "A4") (pinfunction "A4_A4") (pintype "bidirectional"))
      (node (ref "SLOT2") (pin "A4") (pinfunction "A4_A4") (pintype "bidirectional"))
      (node (ref "SLOT3") (pin "A4") (pinfunction "A4_A4") (pintype "bidirectional"))
      (node (ref "SLOT4") (pin "A4") (pinfunction "A4_A4") (pintype "bidirectional"))
      (node (ref "SLOT5") (pin "A4") (pinfunction "A4_A4") (pintype "bidirectional"))
      (node (ref "SLOT6") (pin "A4") (pinfunction "A4_A4") (pintype "bidirectional"))
      (node (ref "SLOT7") (pin "A4") (pinfunction "A4_A4") (pintype "bidirectional"))
    )
    (net (code "30") (name "/AUX5") (class "Default")
      (node (ref "J14") (pin "6") (pinfunction "6_6") (pintype "passive"))
      (node (ref "R54") (pin "1") (pinfunction "1_1") (pintype "passive"))
      (node (ref "SLOT0") (pin "B4") (pinfunction "B4_B4") (pintype "bidirectional"))
      (node (ref "SLOT1") (pin "B4") (pinfunction "B4_B4") (pintype "bidirectional"))
      (node (ref "SLOT2") (pin "B4") (pinfunction "B4_B4") (pintype "bidirectional"))
      (node (ref "SLOT3") (pin "B4") (pinfunction "B4_B4") (pintype "bidirectional"))
      (node (ref "SLOT4") (pin "B4") (pinfunction "B4_B4") (pintype "bidirectional"))
      (node (ref "SLOT5") (pin "B4") (pinfunction "B4_B4") (pintype "bidirectional"))
      (node (ref "SLOT6") (pin "B4") (pinfunction "B4_B4") (pintype "bidirectional"))
      (node (ref "SLOT7") (pin "B4") (pinfunction "B4_B4") (pintype "bidirectional"))
    )
    (net (code "31") (name "/AUX6") (class "Default")
      (node (ref "J14") (pin "7") (pinfunction "7_7") (pintype "passive"))
      (node (ref "R55") (pin "1") (pinfunction "1_1") (pintype "passive"))
      (node (ref "SLOT0") (pin "A5") (pinfunction "A5_A5") (pintype "bidirectional"))
      (node (ref "SLOT1") (pin "A5") (pinfunction "A5_A5") (pintype "bidirectional"))
      (node (ref "SLOT2") (pin "A5") (pinfunction "A5_A5") (pintype "bidirectional"))
      (node (ref "SLOT3") (pin "A5") (pinfunction "A5_A5") (pintype "bidirectional"))
      (node (ref "SLOT4") (pin "A5") (pinfunction "A5_A5") (pintype "bidirectional"))
      (node (ref "SLOT5") (pin "A5") (pinfunction "A5_A5") (pintype "bidirectional"))
      (node (ref "SLOT6") (pin "A5") (pinfunction "A5_A5") (pintype "bidirectional"))
      (node (ref "SLOT7") (pin "A5") (pinfunction "A5_A5") (pintype "bidirectional"))
    )
    (net (code "32") (name "/AUX7") (class "Default")
      (node (ref "J14") (pin "8") (pinfunction "8_8") (pintype "passive"))
      (node (ref "R56") (pin "1") (pinfunction "1_1") (pintype "passive"))
      (node (ref "SLOT0") (pin "B5") (pinfunction "B5_B5") (pintype "bidirectional"))
      (node (ref "SLOT1") (pin "B5") (pinfunction "B5_B5") (pintype "bidirectional"))
      (node (ref "SLOT2") (pin "B5") (pinfunction "B5_B5") (pintype "bidirectional"))
      (node (ref "SLOT3") (pin "B5") (pinfunction "B5_B5") (pintype "bidirectional"))
      (node (ref "SLOT4") (pin "B5") (pinfunction "B5_B5") (pintype "bidirectional"))
      (node (ref "SLOT5") (pin "B5") (pinfunction "B5_B5") (pintype "bidirectional"))
      (node (ref "SLOT6") (pin "B5") (pinfunction "B5_B5") (pintype "bidirectional"))
      (node (ref "SLOT7") (pin "B5") (pinfunction "B5_B5") (pintype "bidirectional"))
    )
    (net (code "33") (name "/CC1") (class "Default")
      (node (ref "J16") (pin "A5") (pinfunction "CC1_A5") (pintype "bidirectional"))
      (node (ref "R57") (pin "2") (pinfunction "2_2") (pintype "passive"))
    )
    (net (code "34") (name "/CC2") (class "Default")
      (node (ref "J16") (pin "B5") (pinfunction "CC2_B5") (pintype "bidirectional"))
      (node (ref "R58") (pin "2") (pinfunction "2_2") (pintype "passive"))
    )
    (net (code "35") (name "/CLK") (class "Default")
      (node (ref "SLOT0") (pin "A14") (pinfunction "A14_A14") (pintype "bidirectional"))
      (node (ref "SLOT1") (pin "A14") (pinfunction "A14_A14") (pintype "bidirectional"))
      (node (ref "SLOT2") (pin "A14") (pinfunction "A14_A14") (pintype "bidirectional"))
      (node (ref "SLOT3") (pin "A14") (pinfunction "A14_A14") (pintype "bidirectional"))
      (node (ref "SLOT4") (pin "A14") (pinfunction "A14_A14") (pintype "bidirectional"))
      (node (ref "SLOT5") (pin "A14") (pinfunction "A14_A14") (pintype "bidirectional"))
      (node (ref "SLOT6") (pin "A14") (pinfunction "A14_A14") (pintype "bidirectional"))
      (node (ref "SLOT7") (pin "A14") (pinfunction "A14_A14") (pintype "bidirectional"))
    )
    (net (code "36") (name "/D0") (class "Default")
      (node (ref "J9") (pin "1") (pinfunction "1_1") (pintype "passive"))
      (node (ref "R9") (pin "1") (pinfunction "1_1") (pintype "passive"))
      (node (ref "SLOT0") (pin "A16") (pinfunction "A16_A16") (pintype "bidirectional"))
      (node (ref "SLOT1") (pin "A16") (pinfunction "A16_A16") (pintype "bidirectional"))
      (node (ref "SLOT2") (pin "A16") (pinfunction "A16_A16") (pintype "bidirectional"))
      (node (ref "SLOT3") (pin "A16") (pinfunction "A16_A16") (pintype "bidirectional"))
      (node (ref "SLOT4") (pin "A16") (pinfunction "A16_A16") (pintype "bidirectional"))
      (node (ref "SLOT5") (pin "A16") (pinfunction "A16_A16") (pintype "bidirectional"))
      (node (ref "SLOT6") (pin "A16") (pinfunction "A16_A16") (pintype "bidirectional"))
      (node (ref "SLOT7") (pin "A16") (pinfunction "A16_A16") (pintype "bidirectional"))
    )
    (net (code "37") (name "/D1") (class "Default")
      (node (ref "J9") (pin "2") (pinfunction "2_2") (pintype "passive"))
      (node (ref "R10") (pin "1") (pinfunction "1_1") (pintype "passive"))
      (node (ref "SLOT0") (pin "B16") (pinfunction "B16_B16") (pintype "bidirectional"))
      (node (ref "SLOT1") (pin "B16") (pinfunction "B16_B16") (pintype "bidirectional"))
      (node (ref "SLOT2") (pin "B16") (pinfunction "B16_B16") (pintype "bidirectional"))
      (node (ref "SLOT3") (pin "B16") (pinfunction "B16_B16") (pintype "bidirectional"))
      (node (ref "SLOT4") (pin "B16") (pinfunction "B16_B16") (pintype "bidirectional"))
      (node (ref "SLOT5") (pin "B16") (pinfunction "B16_B16") (pintype "bidirectional"))
      (node (ref "SLOT6") (pin "B16") (pinfunction "B16_B16") (pintype "bidirectional"))
      (node (ref "SLOT7") (pin "B16") (pinfunction "B16_B16") (pintype "bidirectional"))
    )
    (net (code "38") (name "/D2") (class "Default")
      (node (ref "J9") (pin "3") (pinfunction "3_3") (pintype "passive"))
      (node (ref "R11") (pin "1") (pinfunction "1_1") (pintype "passive"))
      (node (ref "SLOT0") (pin "A17") (pinfunction "A17_A17") (pintype "bidirectional"))
      (node (ref "SLOT1") (pin "A17") (pinfunction "A17_A17") (pintype "bidirectional"))
      (node (ref "SLOT2") (pin "A17") (pinfunction "A17_A17") (pintype "bidirectional"))
      (node (ref "SLOT3") (pin "A17") (pinfunction "A17_A17") (pintype "bidirectional"))
      (node (ref "SLOT4") (pin "A17") (pinfunction "A17_A17") (pintype "bidirectional"))
      (node (ref "SLOT5") (pin "A17") (pinfunction "A17_A17") (pintype "bidirectional"))
      (node (ref "SLOT6") (pin "A17") (pinfunction "A17_A17") (pintype "bidirectional"))
      (node (ref "SLOT7") (pin "A17") (pinfunction "A17_A17") (pintype "bidirectional"))
    )
    (net (code "39") (name "/D3") (class "Default")
      (node (ref "J9") (pin "4") (pinfunction "4_4") (pintype "passive"))
      (node (ref "R12") (pin "1") (pinfunction "1_1") (pintype "passive"))
      (node (ref "SLOT0") (pin "B17") (pinfunction "B17_B17") (pintype "bidirectional"))
      (node (ref "SLOT1") (pin "B17") (pinfunction "B17_B17") (pintype "bidirectional"))
      (node (ref "SLOT2") (pin "B17") (pinfunction "B17_B17") (pintype "bidirectional"))
      (node (ref "SLOT3") (pin "B17") (pinfunction "B17_B17") (pintype "bidirectional"))
      (node (ref "SLOT4") (pin "B17") (pinfunction "B17_B17") (pintype "bidirectional"))
      (node (ref "SLOT5") (pin "B17") (pinfunction "B17_B17") (pintype "bidirectional"))
      (node (ref "SLOT6") (pin "B17") (pinfunction "B17_B17") (pintype "bidirectional"))
      (node (ref "SLOT7") (pin "B17") (pinfunction "B17_B17") (pintype "bidirectional"))
    )
    (net (code "40") (name "/D4") (class "Default")
      (node (ref "J9") (pin "5") (pinfunction "5_5") (pintype "passive"))
      (node (ref "R13") (pin "1") (pinfunction "1_1") (pintype "passive"))
      (node (ref "SLOT0") (pin "A18") (pinfunction "A18_A18") (pintype "bidirectional"))
      (node (ref "SLOT1") (pin "A18") (pinfunction "A18_A18") (pintype "bidirectional"))
      (node (ref "SLOT2") (pin "A18") (pinfunction "A18_A18") (pintype "bidirectional"))
      (node (ref "SLOT3") (pin "A18") (pinfunction "A18_A18") (pintype "bidirectional"))
      (node (ref "SLOT4") (pin "A18") (pinfunction "A18_A18") (pintype "bidirectional"))
      (node (ref "SLOT5") (pin "A18") (pinfunction "A18_A18") (pintype "bidirectional"))
      (node (ref "SLOT6") (pin "A18") (pinfunction "A18_A18") (pintype "bidirectional"))
      (node (ref "SLOT7") (pin "A18") (pinfunction "A18_A18") (pintype "bidirectional"))
    )
    (net (code "41") (name "/D5") (class "Default")
      (node (ref "J9") (pin "6") (pinfunction "6_6") (pintype "passive"))
      (node (ref "R14") (pin "1") (pinfunction "1_1") (pintype "passive"))
      (node (ref "SLOT0") (pin "B18") (pinfunction "B18_B18") (pintype "bidirectional"))
      (node (ref "SLOT1") (pin "B18") (pinfunction "B18_B18") (pintype "bidirectional"))
      (node (ref "SLOT2") (pin "B18") (pinfunction "B18_B18") (pintype "bidirectional"))
      (node (ref "SLOT3") (pin "B18") (pinfunction "B18_B18") (pintype "bidirectional"))
      (node (ref "SLOT4") (pin "B18") (pinfunction "B18_B18") (pintype "bidirectional"))
      (node (ref "SLOT5") (pin "B18") (pinfunction "B18_B18") (pintype "bidirectional"))
      (node (ref "SLOT6") (pin "B18") (pinfunction "B18_B18") (pintype "bidirectional"))
      (node (ref "SLOT7") (pin "B18") (pinfunction "B18_B18") (pintype "bidirectional"))
    )
    (net (code "42") (name "/D6") (class "Default")
      (node (ref "J9") (pin "7") (pinfunction "7_7") (pintype "passive"))
      (node (ref "R15") (pin "1") (pinfunction "1_1") (pintype "passive"))
      (node (ref "SLOT0") (pin "A19") (pinfunction "A19_A19") (pintype "bidirectional"))
      (node (ref "SLOT1") (pin "A19") (pinfunction "A19_A19") (pintype "bidirectional"))
      (node (ref "SLOT2") (pin "A19") (pinfunction "A19_A19") (pintype "bidirectional"))
      (node (ref "SLOT3") (pin "A19") (pinfunction "A19_A19") (pintype "bidirectional"))
      (node (ref "SLOT4") (pin "A19") (pinfunction "A19_A19") (pintype "bidirectional"))
      (node (ref "SLOT5") (pin "A19") (pinfunction "A19_A19") (pintype "bidirectional"))
      (node (ref "SLOT6") (pin "A19") (pinfunction "A19_A19") (pintype "bidirectional"))
      (node (ref "SLOT7") (pin "A19") (pinfunction "A19_A19") (pintype "bidirectional"))
    )
    (net (code "43") (name "/D7") (class "Default")
      (node (ref "J9") (pin "8") (pinfunction "8_8") (pintype "passive"))
      (node (ref "R16") (pin "1") (pinfunction "1_1") (pintype "passive"))
      (node (ref "SLOT0") (pin "B19") (pinfunction "B19_B19") (pintype "bidirectional"))
      (node (ref "SLOT1") (pin "B19") (pinfunction "B19_B19") (pintype "bidirectional"))
      (node (ref "SLOT2") (pin "B19") (pinfunction "B19_B19") (pintype "bidirectional"))
      (node (ref "SLOT3") (pin "B19") (pinfunction "B19_B19") (pintype "bidirectional"))
      (node (ref "SLOT4") (pin "B19") (pinfunction "B19_B19") (pintype "bidirectional"))
      (node (ref "SLOT5") (pin "B19") (pinfunction "B19_B19") (pintype "bidirectional"))
      (node (ref "SLOT6") (pin "B19") (pinfunction "B19_B19") (pintype "bidirectional"))
      (node (ref "SLOT7") (pin "B19") (pinfunction "B19_B19") (pintype "bidirectional"))
    )
    (net (code "44") (name "/FX") (class "Default")
      (node (ref "M1") (pin "D7") (pinfunction "D7_D7") (pintype "bidirectional"))
      (node (ref "R62") (pin "1") (pinfunction "1_1") (pintype "passive"))
    )
    (net (code "45") (name "/RX") (class "Default")
      (node (ref "M1") (pin "D0") (pinfunction "D0_D0") (pintype "bidirectional"))
      (node (ref "SERIAL") (pin "2") (pinfunction "2_2") (pintype "passive"))
    )
    (net (code "46") (name "/SVC_CK") (class "Default")
      (node (ref "J15") (pin "2") (pinfunction "2_2") (pintype "passive"))
      (node (ref "M1") (pin "A5") (pinfunction "A5_A5") (pintype "bidirectional"))
      (node (ref "R60") (pin "1") (pinfunction "1_1") (pintype "passive"))
      (node (ref "SLOT0") (pin "B1") (pinfunction "B1_B1") (pintype "bidirectional"))
      (node (ref "SLOT1") (pin "B1") (pinfunction "B1_B1") (pintype "bidirectional"))
      (node (ref "SLOT2") (pin "B1") (pinfunction "B1_B1") (pintype "bidirectional"))
      (node (ref "SLOT3") (pin "B1") (pinfunction "B1_B1") (pintype "bidirectional"))
      (node (ref "SLOT4") (pin "B1") (pinfunction "B1_B1") (pintype "bidirectional"))
      (node (ref "SLOT5") (pin "B1") (pinfunction "B1_B1") (pintype "bidirectional"))
      (node (ref "SLOT6") (pin "B1") (pinfunction "B1_B1") (pintype "bidirectional"))
      (node (ref "SLOT7") (pin "B1") (pinfunction "B1_B1") (pintype "bidirectional"))
    )
    (net (code "47") (name "/SVC_DA") (class "Default")
      (node (ref "J15") (pin "1") (pinfunction "1_1") (pintype "passive"))
      (node (ref "M1") (pin "A4") (pinfunction "A4_A4") (pintype "bidirectional"))
      (node (ref "R61") (pin "1") (pinfunction "1_1") (pintype "passive"))
      (node (ref "SLOT0") (pin "A1") (pinfunction "A1_A1") (pintype "bidirectional"))
      (node (ref "SLOT1") (pin "A1") (pinfunction "A1_A1") (pintype "bidirectional"))
      (node (ref "SLOT2") (pin "A1") (pinfunction "A1_A1") (pintype "bidirectional"))
      (node (ref "SLOT3") (pin "A1") (pinfunction "A1_A1") (pintype "bidirectional"))
      (node (ref "SLOT4") (pin "A1") (pinfunction "A1_A1") (pintype "bidirectional"))
      (node (ref "SLOT5") (pin "A1") (pinfunction "A1_A1") (pintype "bidirectional"))
      (node (ref "SLOT6") (pin "A1") (pinfunction "A1_A1") (pintype "bidirectional"))
      (node (ref "SLOT7") (pin "A1") (pinfunction "A1_A1") (pintype "bidirectional"))
    )
    (net (code "48") (name "/TX") (class "Default")
      (node (ref "M1") (pin "D1") (pinfunction "D1_D1") (pintype "bidirectional"))
      (node (ref "SERIAL") (pin "1") (pinfunction "1_1") (pintype "passive"))
    )
    (net (code "49") (name "/VBUS") (class "Default")
      (node (ref "J16") (pin "A9") (pinfunction "VBUS_A9") (pintype "power_in"))
      (node (ref "J16") (pin "B9") (pinfunction "VBUS_B9") (pintype "power_in"))
      (node (ref "P_SW") (pin "2") (pinfunction "2_2") (pintype "passive"))
    )
    (net (code "50") (name "/WAIT") (class "Default")
      (node (ref "J13") (pin "1") (pinfunction "1_1") (pintype "passive"))
      (node (ref "R41") (pin "1") (pinfunction "1_1") (pintype "passive"))
      (node (ref "SLOT0") (pin "B10") (pinfunction "B10_B10") (pintype "bidirectional"))
      (node (ref "SLOT1") (pin "B10") (pinfunction "B10_B10") (pintype "bidirectional"))
      (node (ref "SLOT2") (pin "B10") (pinfunction "B10_B10") (pintype "bidirectional"))
      (node (ref "SLOT3") (pin "B10") (pinfunction "B10_B10") (pintype "bidirectional"))
      (node (ref "SLOT4") (pin "B10") (pinfunction "B10_B10") (pintype "bidirectional"))
      (node (ref "SLOT5") (pin "B10") (pinfunction "B10_B10") (pintype "bidirectional"))
      (node (ref "SLOT6") (pin "B10") (pinfunction "B10_B10") (pintype "bidirectional"))
      (node (ref "SLOT7") (pin "B10") (pinfunction "B10_B10") (pintype "bidirectional"))
    )
    (net (code "51") (name "/~{CLK}") (class "Default")
      (node (ref "SLOT0") (pin "B14") (pinfunction "B14_B14") (pintype "bidirectional"))
      (node (ref "SLOT1") (pin "B14") (pinfunction "B14_B14") (pintype "bidirectional"))
      (node (ref "SLOT2") (pin "B14") (pinfunction "B14_B14") (pintype "bidirectional"))
      (node (ref "SLOT3") (pin "B14") (pinfunction "B14_B14") (pintype "bidirectional"))
      (node (ref "SLOT4") (pin "B14") (pinfunction "B14_B14") (pintype "bidirectional"))
      (node (ref "SLOT5") (pin "B14") (pinfunction "B14_B14") (pintype "bidirectional"))
      (node (ref "SLOT6") (pin "B14") (pinfunction "B14_B14") (pintype "bidirectional"))
      (node (ref "SLOT7") (pin "B14") (pinfunction "B14_B14") (pintype "bidirectional"))
    )
    (net (code "52") (name "/~{INT}") (class "Default")
      (node (ref "J13") (pin "4") (pinfunction "4_4") (pintype "passive"))
      (node (ref "R44") (pin "1") (pinfunction "1_1") (pintype "passive"))
      (node (ref "SLOT0") (pin "A11") (pinfunction "A11_A11") (pintype "bidirectional"))
      (node (ref "SLOT1") (pin "A11") (pinfunction "A11_A11") (pintype "bidirectional"))
      (node (ref "SLOT2") (pin "A11") (pinfunction "A11_A11") (pintype "bidirectional"))
      (node (ref "SLOT3") (pin "A11") (pinfunction "A11_A11") (pintype "bidirectional"))
      (node (ref "SLOT4") (pin "A11") (pinfunction "A11_A11") (pintype "bidirectional"))
      (node (ref "SLOT5") (pin "A11") (pinfunction "A11_A11") (pintype "bidirectional"))
      (node (ref "SLOT6") (pin "A11") (pinfunction "A11_A11") (pintype "bidirectional"))
      (node (ref "SLOT7") (pin "A11") (pinfunction "A11_A11") (pintype "bidirectional"))
    )
    (net (code "53") (name "/~{IORQ}") (class "Default")
      (node (ref "J13") (pin "7") (pinfunction "7_7") (pintype "passive"))
      (node (ref "R47") (pin "1") (pinfunction "1_1") (pintype "passive"))
      (node (ref "SLOT0") (pin "B13") (pinfunction "B13_B13") (pintype "bidirectional"))
      (node (ref "SLOT1") (pin "B13") (pinfunction "B13_B13") (pintype "bidirectional"))
      (node (ref "SLOT2") (pin "B13") (pinfunction "B13_B13") (pintype "bidirectional"))
      (node (ref "SLOT3") (pin "B13") (pinfunction "B13_B13") (pintype "bidirectional"))
      (node (ref "SLOT4") (pin "B13") (pinfunction "B13_B13") (pintype "bidirectional"))
      (node (ref "SLOT5") (pin "B13") (pinfunction "B13_B13") (pintype "bidirectional"))
      (node (ref "SLOT6") (pin "B13") (pinfunction "B13_B13") (pintype "bidirectional"))
      (node (ref "SLOT7") (pin "B13") (pinfunction "B13_B13") (pintype "bidirectional"))
    )
    (net (code "54") (name "/~{MRQ}") (class "Default")
      (node (ref "J13") (pin "8") (pinfunction "8_8") (pintype "passive"))
      (node (ref "R48") (pin "1") (pinfunction "1_1") (pintype "passive"))
      (node (ref "SLOT0") (pin "A13") (pinfunction "A13_A13") (pintype "bidirectional"))
      (node (ref "SLOT1") (pin "A13") (pinfunction "A13_A13") (pintype "bidirectional"))
      (node (ref "SLOT2") (pin "A13") (pinfunction "A13_A13") (pintype "bidirectional"))
      (node (ref "SLOT3") (pin "A13") (pinfunction "A13_A13") (pintype "bidirectional"))
      (node (ref "SLOT4") (pin "A13") (pinfunction "A13_A13") (pintype "bidirectional"))
      (node (ref "SLOT5") (pin "A13") (pinfunction "A13_A13") (pintype "bidirectional"))
      (node (ref "SLOT6") (pin "A13") (pinfunction "A13_A13") (pintype "bidirectional"))
      (node (ref "SLOT7") (pin "A13") (pinfunction "A13_A13") (pintype "bidirectional"))
    )
    (net (code "55") (name "/~{NMI}") (class "Default")
      (node (ref "J13") (pin "3") (pinfunction "3_3") (pintype "passive"))
      (node (ref "R43") (pin "1") (pinfunction "1_1") (pintype "passive"))
      (node (ref "SLOT0") (pin "B11") (pinfunction "B11_B11") (pintype "bidirectional"))
      (node (ref "SLOT1") (pin "B11") (pinfunction "B11_B11") (pintype "bidirectional"))
      (node (ref "SLOT2") (pin "B11") (pinfunction "B11_B11") (pintype "bidirectional"))
      (node (ref "SLOT3") (pin "B11") (pinfunction "B11_B11") (pintype "bidirectional"))
      (node (ref "SLOT4") (pin "B11") (pinfunction "B11_B11") (pintype "bidirectional"))
      (node (ref "SLOT5") (pin "B11") (pinfunction "B11_B11") (pintype "bidirectional"))
      (node (ref "SLOT6") (pin "B11") (pinfunction "B11_B11") (pintype "bidirectional"))
      (node (ref "SLOT7") (pin "B11") (pinfunction "B11_B11") (pintype "bidirectional"))
    )
    (net (code "56") (name "/~{RST}") (class "Default")
      (node (ref "C20") (pin "1") (pinfunction "1_1") (pintype "passive"))
      (node (ref "ICSP") (pin "5") (pinfunction "5_5") (pintype "passive"))
      (node (ref "J15") (pin "3") (pinfunction "3_3") (pintype "passive"))
      (node (ref "M1") (pin "!RESET") (pinfunction "~{RESET}_!RESET") (pintype "bidirectional"))
      (node (ref "R59") (pin "1") (pinfunction "1_1") (pintype "passive"))
      (node (ref "RESET") (pin "1") (pinfunction "1_1") (pintype "passive"))
      (node (ref "RESET") (pin "2") (pinfunction "1_2") (pintype "passive"))
      (node (ref "RST_EXT") (pin "1") (pinfunction "1_1") (pintype "passive"))
      (node (ref "SLOT0") (pin "A9") (pinfunction "A9_A9") (pintype "bidirectional"))
      (node (ref "SLOT1") (pin "A9") (pinfunction "A9_A9") (pintype "bidirectional"))
      (node (ref "SLOT2") (pin "A9") (pinfunction "A9_A9") (pintype "bidirectional"))
      (node (ref "SLOT3") (pin "A9") (pinfunction "A9_A9") (pintype "bidirectional"))
      (node (ref "SLOT4") (pin "A9") (pinfunction "A9_A9") (pintype "bidirectional"))
      (node (ref "SLOT5") (pin "A9") (pinfunction "A9_A9") (pintype "bidirectional"))
      (node (ref "SLOT6") (pin "A9") (pinfunction "A9_A9") (pintype "bidirectional"))
      (node (ref "SLOT7") (pin "A9") (pinfunction "A9_A9") (pintype "bidirectional"))
      (node (ref "U1") (pin "2") (pinfunction "~{RST}_2") (pintype "output"))
    )
    (net (code "57") (name "/~{R}") (class "Default")
      (node (ref "J13") (pin "6") (pinfunction "6_6") (pintype "passive"))
      (node (ref "R46") (pin "1") (pinfunction "1_1") (pintype "passive"))
      (node (ref "SLOT0") (pin "A12") (pinfunction "A12_A12") (pintype "bidirectional"))
      (node (ref "SLOT1") (pin "A12") (pinfunction "A12_A12") (pintype "bidirectional"))
      (node (ref "SLOT2") (pin "A12") (pinfunction "A12_A12") (pintype "bidirectional"))
      (node (ref "SLOT3") (pin "A12") (pinfunction "A12_A12") (pintype "bidirectional"))
      (node (ref "SLOT4") (pin "A12") (pinfunction "A12_A12") (pintype "bidirectional"))
      (node (ref "SLOT5") (pin "A12") (pinfunction "A12_A12") (pintype "bidirectional"))
      (node (ref "SLOT6") (pin "A12") (pinfunction "A12_A12") (pintype "bidirectional"))
      (node (ref "SLOT7") (pin "A12") (pinfunction "A12_A12") (pintype "bidirectional"))
    )
    (net (code "58") (name "/~{T1}") (class "Default")
      (node (ref "J13") (pin "2") (pinfunction "2_2") (pintype "passive"))
      (node (ref "R42") (pin "1") (pinfunction "1_1") (pintype "passive"))
      (node (ref "SLOT0") (pin "A10") (pinfunction "A10_A10") (pintype "bidirectional"))
      (node (ref "SLOT1") (pin "A10") (pinfunction "A10_A10") (pintype "bidirectional"))
      (node (ref "SLOT2") (pin "A10") (pinfunction "A10_A10") (pintype "bidirectional"))
      (node (ref "SLOT3") (pin "A10") (pinfunction "A10_A10") (pintype "bidirectional"))
      (node (ref "SLOT4") (pin "A10") (pinfunction "A10_A10") (pintype "bidirectional"))
      (node (ref "SLOT5") (pin "A10") (pinfunction "A10_A10") (pintype "bidirectional"))
      (node (ref "SLOT6") (pin "A10") (pinfunction "A10_A10") (pintype "bidirectional"))
      (node (ref "SLOT7") (pin "A10") (pinfunction "A10_A10") (pintype "bidirectional"))
    )
    (net (code "59") (name "/~{W}") (class "Default")
      (node (ref "J13") (pin "5") (pinfunction "5_5") (pintype "passive"))
      (node (ref "R45") (pin "1") (pinfunction "1_1") (pintype "passive"))
      (node (ref "SLOT0") (pin "B12") (pinfunction "B12_B12") (pintype "bidirectional"))
      (node (ref "SLOT1") (pin "B12") (pinfunction "B12_B12") (pintype "bidirectional"))
      (node (ref "SLOT2") (pin "B12") (pinfunction "B12_B12") (pintype "bidirectional"))
      (node (ref "SLOT3") (pin "B12") (pinfunction "B12_B12") (pintype "bidirectional"))
      (node (ref "SLOT4") (pin "B12") (pinfunction "B12_B12") (pintype "bidirectional"))
      (node (ref "SLOT5") (pin "B12") (pinfunction "B12_B12") (pintype "bidirectional"))
      (node (ref "SLOT6") (pin "B12") (pinfunction "B12_B12") (pintype "bidirectional"))
      (node (ref "SLOT7") (pin "B12") (pinfunction "B12_B12") (pintype "bidirectional"))
    )
    (net (code "60") (name "GND") (class "Default")
      (node (ref "!INT") (pin "K") (pinfunction "C_K") (pintype "passive"))
      (node (ref "!IORQ") (pin "K") (pinfunction "C_K") (pintype "passive"))
      (node (ref "!MRQ") (pin "K") (pinfunction "C_K") (pintype "passive"))
      (node (ref "!NMI") (pin "K") (pinfunction "C_K") (pintype "passive"))
      (node (ref "!R") (pin "K") (pinfunction "C_K") (pintype "passive"))
      (node (ref "!T1") (pin "K") (pinfunction "C_K") (pintype "passive"))
      (node (ref "!W") (pin "K") (pinfunction "C_K") (pintype "passive"))
      (node (ref "AD0") (pin "K") (pinfunction "C_K") (pintype "passive"))
      (node (ref "AD1") (pin "K") (pinfunction "C_K") (pintype "passive"))
      (node (ref "AD10") (pin "K") (pinfunction "C_K") (pintype "passive"))
      (node (ref "AD11") (pin "K") (pinfunction "C_K") (pintype "passive"))
      (node (ref "AD12") (pin "K") (pinfunction "C_K") (pintype "passive"))
      (node (ref "AD13") (pin "K") (pinfunction "C_K") (pintype "passive"))
      (node (ref "AD14") (pin "K") (pinfunction "C_K") (pintype "passive"))
      (node (ref "AD15") (pin "K") (pinfunction "C_K") (pintype "passive"))
      (node (ref "AD16") (pin "K") (pinfunction "C_K") (pintype "passive"))
      (node (ref "AD17") (pin "K") (pinfunction "C_K") (pintype "passive"))
      (node (ref "AD18") (pin "K") (pinfunction "C_K") (pintype "passive"))
      (node (ref "AD19") (pin "K") (pinfunction "C_K") (pintype "passive"))
      (node (ref "AD2") (pin "K") (pinfunction "C_K") (pintype "passive"))
      (node (ref "AD20") (pin "K") (pinfunction "C_K") (pintype "passive"))
      (node (ref "AD21") (pin "K") (pinfunction "C_K") (pintype "passive"))
      (node (ref "AD22") (pin "K") (pinfunction "C_K") (pintype "passive"))
      (node (ref "AD23") (pin "K") (pinfunction "C_K") (pintype "passive"))
      (node (ref "AD3") (pin "K") (pinfunction "C_K") (pintype "passive"))
      (node (ref "AD4") (pin "K") (pinfunction "C_K") (pintype "passive"))
      (node (ref "AD5") (pin "K") (pinfunction "C_K") (pintype "passive"))
      (node (ref "AD6") (pin "K") (pinfunction "C_K") (pintype "passive"))
      (node (ref "AD7") (pin "K") (pinfunction "C_K") (pintype "passive"))
      (node (ref "AD8") (pin "K") (pinfunction "C_K") (pintype "passive"))
      (node (ref "AD9") (pin "K") (pinfunction "C_K") (pintype "passive"))
      (node (ref "AUX0") (pin "K") (pinfunction "C_K") (pintype "passive"))
      (node (ref "AUX1") (pin "K") (pinfunction "C_K") (pintype "passive"))
      (node (ref "AUX2") (pin "K") (pinfunction "C_K") (pintype "passive"))
      (node (ref "AUX3") (pin "K") (pinfunction "C_K") (pintype "passive"))
      (node (ref "AUX4") (pin "K") (pinfunction "C_K") (pintype "passive"))
      (node (ref "AUX5") (pin "K") (pinfunction "C_K") (pintype "passive"))
      (node (ref "AUX6") (pin "K") (pinfunction "C_K") (pintype "passive"))
      (node (ref "AUX7") (pin "K") (pinfunction "C_K") (pintype "passive"))
      (node (ref "C1") (pin "2") (pinfunction "2_2") (pintype "passive"))
      (node (ref "C10") (pin "2") (pinfunction "2_2") (pintype "passive"))
      (node (ref "C11") (pin "2") (pinfunction "2_2") (pintype "passive"))
      (node (ref "C12") (pin "2") (pinfunction "2_2") (pintype "passive"))
      (node (ref "C13") (pin "2") (pinfunction "2_2") (pintype "passive"))
      (node (ref "C14") (pin "2") (pinfunction "2_2") (pintype "passive"))
      (node (ref "C2") (pin "2") (pinfunction "2_2") (pintype "passive"))
      (node (ref "C20") (pin "2") (pinfunction "2_2") (pintype "passive"))
      (node (ref "C3") (pin "2") (pinfunction "2_2") (pintype "passive"))
      (node (ref "C4") (pin "2") (pinfunction "2_2") (pintype "passive"))
      (node (ref "C5") (pin "2") (pinfunction "2_2") (pintype "passive"))
      (node (ref "C6") (pin "2") (pinfunction "2_2") (pintype "passive"))
      (node (ref "C7") (pin "2") (pinfunction "2_2") (pintype "passive"))
      (node (ref "C8") (pin "2") (pinfunction "2_2") (pintype "passive"))
      (node (ref "C9") (pin "2") (pinfunction "2_2") (pintype "passive"))
      (node (ref "DAT0") (pin "K") (pinfunction "C_K") (pintype "passive"))
      (node (ref "DAT1") (pin "K") (pinfunction "C_K") (pintype "passive"))
      (node (ref "DAT2") (pin "K") (pinfunction "C_K") (pintype "passive"))
      (node (ref "DAT3") (pin "K") (pinfunction "C_K") (pintype "passive"))
      (node (ref "DAT4") (pin "K") (pinfunction "C_K") (pintype "passive"))
      (node (ref "DAT5") (pin "K") (pinfunction "C_K") (pintype "passive"))
      (node (ref "DAT6") (pin "K") (pinfunction "C_K") (pintype "passive"))
      (node (ref "DAT7") (pin "K") (pinfunction "C_K") (pintype "passive"))
      (node (ref "ICSP") (pin "6") (pinfunction "6_6") (pintype "passive"))
      (node (ref "J15") (pin "5") (pinfunction "5_5") (pintype "passive"))
      (node (ref "J15") (pin "6") (pinfunction "6_6") (pintype "passive"))
      (node (ref "J15") (pin "7") (pinfunction "7_7") (pintype "passive"))
      (node (ref "J15") (pin "8") (pinfunction "8_8") (pintype "passive"))
      (node (ref "J16") (pin "A12") (pinfunction "GND_A12") (pintype "power_in"))
      (node (ref "J16") (pin "B12") (pinfunction "GND_B12") (pintype "power_in"))
      (node (ref "M1") (pin "GND") (pinfunction "GND_GND") (pintype "bidirectional"))
      (node (ref "R1") (pin "2") (pinfunction "2_2") (pintype "passive"))
      (node (ref "R2") (pin "2") (pinfunction "2_2") (pintype "passive"))
      (node (ref "R3") (pin "2") (pinfunction "2_2") (pintype "passive"))
      (node (ref "R4") (pin "2") (pinfunction "2_2") (pintype "passive"))
      (node (ref "R5") (pin "2") (pinfunction "2_2") (pintype "passive"))
      (node (ref "R57") (pin "1") (pinfunction "1_1") (pintype "passive"))
      (node (ref "R58") (pin "1") (pinfunction "1_1") (pintype "passive"))
      (node (ref "R6") (pin "2") (pinfunction "2_2") (pintype "passive"))
      (node (ref "R7") (pin "2") (pinfunction "2_2") (pintype "passive"))
      (node (ref "R8") (pin "2") (pinfunction "2_2") (pintype "passive"))
      (node (ref "RESET") (pin "3") (pinfunction "2_3") (pintype "passive"))
      (node (ref "RESET") (pin "4") (pinfunction "2_4") (pintype "passive"))
      (node (ref "RGB0") (pin "4") (pinfunction "GND_4") (pintype "bidirectional"))
      (node (ref "RGB1") (pin "4") (pinfunction "GND_4") (pintype "bidirectional"))
      (node (ref "RGB10") (pin "4") (pinfunction "GND_4") (pintype "bidirectional"))
      (node (ref "RGB11") (pin "4") (pinfunction "GND_4") (pintype "bidirectional"))
      (node (ref "RGB12") (pin "4") (pinfunction "GND_4") (pintype "bidirectional"))
      (node (ref "RGB13") (pin "4") (pinfunction "GND_4") (pintype "bidirectional"))
      (node (ref "RGB2") (pin "4") (pinfunction "GND_4") (pintype "bidirectional"))
      (node (ref "RGB3") (pin "4") (pinfunction "GND_4") (pintype "bidirectional"))
      (node (ref "RGB4") (pin "4") (pinfunction "GND_4") (pintype "bidirectional"))
      (node (ref "RGB5") (pin "4") (pinfunction "GND_4") (pintype "bidirectional"))
      (node (ref "RGB6") (pin "4") (pinfunction "GND_4") (pintype "bidirectional"))
      (node (ref "RGB7") (pin "4") (pinfunction "GND_4") (pintype "bidirectional"))
      (node (ref "RGB8") (pin "4") (pinfunction "GND_4") (pintype "bidirectional"))
      (node (ref "RGB9") (pin "4") (pinfunction "GND_4") (pintype "bidirectional"))
      (node (ref "RST_EXT") (pin "2") (pinfunction "2_2") (pintype "passive"))
      (node (ref "SERIAL") (pin "3") (pinfunction "3_3") (pintype "passive"))
      (node (ref "SLOT0") (pin "A15") (pinfunction "A15_A15") (pintype "bidirectional"))
      (node (ref "SLOT0") (pin "A20") (pinfunction "A20_A20") (pintype "bidirectional"))
      (node (ref "SLOT0") (pin "A8") (pinfunction "A8_A8") (pintype "bidirectional"))
      (node (ref "SLOT0") (pin "B15") (pinfunction "B15_B15") (pintype "bidirectional"))
      (node (ref "SLOT0") (pin "B20") (pinfunction "B20_B20") (pintype "bidirectional"))
      (node (ref "SLOT0") (pin "B8") (pinfunction "B8_B8") (pintype "bidirectional"))
      (node (ref "SLOT1") (pin "A15") (pinfunction "A15_A15") (pintype "bidirectional"))
      (node (ref "SLOT1") (pin "A20") (pinfunction "A20_A20") (pintype "bidirectional"))
      (node (ref "SLOT1") (pin "A8") (pinfunction "A8_A8") (pintype "bidirectional"))
      (node (ref "SLOT1") (pin "B15") (pinfunction "B15_B15") (pintype "bidirectional"))
      (node (ref "SLOT1") (pin "B20") (pinfunction "B20_B20") (pintype "bidirectional"))
      (node (ref "SLOT1") (pin "B8") (pinfunction "B8_B8") (pintype "bidirectional"))
      (node (ref "SLOT2") (pin "A15") (pinfunction "A15_A15") (pintype "bidirectional"))
      (node (ref "SLOT2") (pin "A20") (pinfunction "A20_A20") (pintype "bidirectional"))
      (node (ref "SLOT2") (pin "A8") (pinfunction "A8_A8") (pintype "bidirectional"))
      (node (ref "SLOT2") (pin "B15") (pinfunction "B15_B15") (pintype "bidirectional"))
      (node (ref "SLOT2") (pin "B20") (pinfunction "B20_B20") (pintype "bidirectional"))
      (node (ref "SLOT2") (pin "B8") (pinfunction "B8_B8") (pintype "bidirectional"))
      (node (ref "SLOT3") (pin "A15") (pinfunction "A15_A15") (pintype "bidirectional"))
      (node (ref "SLOT3") (pin "A20") (pinfunction "A20_A20") (pintype "bidirectional"))
      (node (ref "SLOT3") (pin "A8") (pinfunction "A8_A8") (pintype "bidirectional"))
      (node (ref "SLOT3") (pin "B15") (pinfunction "B15_B15") (pintype "bidirectional"))
      (node (ref "SLOT3") (pin "B20") (pinfunction "B20_B20") (pintype "bidirectional"))
      (node (ref "SLOT3") (pin "B8") (pinfunction "B8_B8") (pintype "bidirectional"))
      (node (ref "SLOT4") (pin "A15") (pinfunction "A15_A15") (pintype "bidirectional"))
      (node (ref "SLOT4") (pin "A20") (pinfunction "A20_A20") (pintype "bidirectional"))
      (node (ref "SLOT4") (pin "A8") (pinfunction "A8_A8") (pintype "bidirectional"))
      (node (ref "SLOT4") (pin "B15") (pinfunction "B15_B15") (pintype "bidirectional"))
      (node (ref "SLOT4") (pin "B20") (pinfunction "B20_B20") (pintype "bidirectional"))
      (node (ref "SLOT4") (pin "B8") (pinfunction "B8_B8") (pintype "bidirectional"))
      (node (ref "SLOT5") (pin "A15") (pinfunction "A15_A15") (pintype "bidirectional"))
      (node (ref "SLOT5") (pin "A20") (pinfunction "A20_A20") (pintype "bidirectional"))
      (node (ref "SLOT5") (pin "A8") (pinfunction "A8_A8") (pintype "bidirectional"))
      (node (ref "SLOT5") (pin "B15") (pinfunction "B15_B15") (pintype "bidirectional"))
      (node (ref "SLOT5") (pin "B20") (pinfunction "B20_B20") (pintype "bidirectional"))
      (node (ref "SLOT5") (pin "B8") (pinfunction "B8_B8") (pintype "bidirectional"))
      (node (ref "SLOT6") (pin "A15") (pinfunction "A15_A15") (pintype "bidirectional"))
      (node (ref "SLOT6") (pin "A20") (pinfunction "A20_A20") (pintype "bidirectional"))
      (node (ref "SLOT6") (pin "A8") (pinfunction "A8_A8") (pintype "bidirectional"))
      (node (ref "SLOT6") (pin "B15") (pinfunction "B15_B15") (pintype "bidirectional"))
      (node (ref "SLOT6") (pin "B20") (pinfunction "B20_B20") (pintype "bidirectional"))
      (node (ref "SLOT6") (pin "B8") (pinfunction "B8_B8") (pintype "bidirectional"))
      (node (ref "SLOT7") (pin "A15") (pinfunction "A15_A15") (pintype "bidirectional"))
      (node (ref "SLOT7") (pin "A20") (pinfunction "A20_A20") (pintype "bidirectional"))
      (node (ref "SLOT7") (pin "A8") (pinfunction "A8_A8") (pintype "bidirectional"))
      (node (ref "SLOT7") (pin "B15") (pinfunction "B15_B15") (pintype "bidirectional"))
      (node (ref "SLOT7") (pin "B20") (pinfunction "B20_B20") (pintype "bidirectional"))
      (node (ref "SLOT7") (pin "B8") (pinfunction "B8_B8") (pintype "bidirectional"))
      (node (ref "U1") (pin "1") (pinfunction "GND_1") (pintype "power_in"))
      (node (ref "WAIT") (pin "K") (pinfunction "C_K") (pintype "passive"))
    )
    (net (code "61") (name "Net-(!INT-PadA)") (class "Default")
      (node (ref "!INT") (pin "A") (pinfunction "A_A") (pintype "passive"))
      (node (ref "R44") (pin "2") (pinfunction "2_2") (pintype "passive"))
    )
    (net (code "62") (name "Net-(!IORQ-PadA)") (class "Default")
      (node (ref "!IORQ") (pin "A") (pinfunction "A_A") (pintype "passive"))
      (node (ref "R47") (pin "2") (pinfunction "2_2") (pintype "passive"))
    )
    (net (code "63") (name "Net-(!MRQ-PadA)") (class "Default")
      (node (ref "!MRQ") (pin "A") (pinfunction "A_A") (pintype "passive"))
      (node (ref "R48") (pin "2") (pinfunction "2_2") (pintype "passive"))
    )
    (net (code "64") (name "Net-(!NMI-PadA)") (class "Default")
      (node (ref "!NMI") (pin "A") (pinfunction "A_A") (pintype "passive"))
      (node (ref "R43") (pin "2") (pinfunction "2_2") (pintype "passive"))
    )
    (net (code "65") (name "Net-(!R-PadA)") (class "Default")
      (node (ref "!R") (pin "A") (pinfunction "A_A") (pintype "passive"))
      (node (ref "R46") (pin "2") (pinfunction "2_2") (pintype "passive"))
    )
    (net (code "66") (name "Net-(!T1-PadA)") (class "Default")
      (node (ref "!T1") (pin "A") (pinfunction "A_A") (pintype "passive"))
      (node (ref "R42") (pin "2") (pinfunction "2_2") (pintype "passive"))
    )
    (net (code "67") (name "Net-(!W-PadA)") (class "Default")
      (node (ref "!W") (pin "A") (pinfunction "A_A") (pintype "passive"))
      (node (ref "R45") (pin "2") (pinfunction "2_2") (pintype "passive"))
    )
    (net (code "68") (name "Net-(AD0-PadA)") (class "Default")
      (node (ref "AD0") (pin "A") (pinfunction "A_A") (pintype "passive"))
      (node (ref "R17") (pin "2") (pinfunction "2_2") (pintype "passive"))
    )
    (net (code "69") (name "Net-(AD1-PadA)") (class "Default")
      (node (ref "AD1") (pin "A") (pinfunction "A_A") (pintype "passive"))
      (node (ref "R18") (pin "2") (pinfunction "2_2") (pintype "passive"))
    )
    (net (code "70") (name "Net-(AD2-PadA)") (class "Default")
      (node (ref "AD2") (pin "A") (pinfunction "A_A") (pintype "passive"))
      (node (ref "R19") (pin "2") (pinfunction "2_2") (pintype "passive"))
    )
    (net (code "71") (name "Net-(AD3-PadA)") (class "Default")
      (node (ref "AD3") (pin "A") (pinfunction "A_A") (pintype "passive"))
      (node (ref "R20") (pin "2") (pinfunction "2_2") (pintype "passive"))
    )
    (net (code "72") (name "Net-(AD4-PadA)") (class "Default")
      (node (ref "AD4") (pin "A") (pinfunction "A_A") (pintype "passive"))
      (node (ref "R21") (pin "2") (pinfunction "2_2") (pintype "passive"))
    )
    (net (code "73") (name "Net-(AD5-PadA)") (class "Default")
      (node (ref "AD5") (pin "A") (pinfunction "A_A") (pintype "passive"))
      (node (ref "R22") (pin "2") (pinfunction "2_2") (pintype "passive"))
    )
    (net (code "74") (name "Net-(AD6-PadA)") (class "Default")
      (node (ref "AD6") (pin "A") (pinfunction "A_A") (pintype "passive"))
      (node (ref "R23") (pin "2") (pinfunction "2_2") (pintype "passive"))
    )
    (net (code "75") (name "Net-(AD7-PadA)") (class "Default")
      (node (ref "AD7") (pin "A") (pinfunction "A_A") (pintype "passive"))
      (node (ref "R24") (pin "2") (pinfunction "2_2") (pintype "passive"))
    )
    (net (code "76") (name "Net-(AD8-PadA)") (class "Default")
      (node (ref "AD8") (pin "A") (pinfunction "A_A") (pintype "passive"))
      (node (ref "R25") (pin "2") (pinfunction "2_2") (pintype "passive"))
    )
    (net (code "77") (name "Net-(AD9-PadA)") (class "Default")
      (node (ref "AD9") (pin "A") (pinfunction "A_A") (pintype "passive"))
      (node (ref "R26") (pin "2") (pinfunction "2_2") (pintype "passive"))
    )
    (net (code "78") (name "Net-(AD10-PadA)") (class "Default")
      (node (ref "AD10") (pin "A") (pinfunction "A_A") (pintype "passive"))
      (node (ref "R27") (pin "2") (pinfunction "2_2") (pintype "passive"))
    )
    (net (code "79") (name "Net-(AD11-PadA)") (class "Default")
      (node (ref "AD11") (pin "A") (pinfunction "A_A") (pintype "passive"))
      (node (ref "R28") (pin "2") (pinfunction "2_2") (pintype "passive"))
    )
    (net (code "80") (name "Net-(AD12-PadA)") (class "Default")
      (node (ref "AD12") (pin "A") (pinfunction "A_A") (pintype "passive"))
      (node (ref "R29") (pin "2") (pinfunction "2_2") (pintype "passive"))
    )
    (net (code "81") (name "Net-(AD13-PadA)") (class "Default")
      (node (ref "AD13") (pin "A") (pinfunction "A_A") (pintype "passive"))
      (node (ref "R30") (pin "2") (pinfunction "2_2") (pintype "passive"))
    )
    (net (code "82") (name "Net-(AD14-PadA)") (class "Default")
      (node (ref "AD14") (pin "A") (pinfunction "A_A") (pintype "passive"))
      (node (ref "R31") (pin "2") (pinfunction "2_2") (pintype "passive"))
    )
    (net (code "83") (name "Net-(AD15-PadA)") (class "Default")
      (node (ref "AD15") (pin "A") (pinfunction "A_A") (pintype "passive"))
      (node (ref "R32") (pin "2") (pinfunction "2_2") (pintype "passive"))
    )
    (net (code "84") (name "Net-(AD16-PadA)") (class "Default")
      (node (ref "AD16") (pin "A") (pinfunction "A_A") (pintype "passive"))
      (node (ref "R33") (pin "2") (pinfunction "2_2") (pintype "passive"))
    )
    (net (code "85") (name "Net-(AD17-PadA)") (class "Default")
      (node (ref "AD17") (pin "A") (pinfunction "A_A") (pintype "passive"))
      (node (ref "R34") (pin "2") (pinfunction "2_2") (pintype "passive"))
    )
    (net (code "86") (name "Net-(AD18-PadA)") (class "Default")
      (node (ref "AD18") (pin "A") (pinfunction "A_A") (pintype "passive"))
      (node (ref "R35") (pin "2") (pinfunction "2_2") (pintype "passive"))
    )
    (net (code "87") (name "Net-(AD19-PadA)") (class "Default")
      (node (ref "AD19") (pin "A") (pinfunction "A_A") (pintype "passive"))
      (node (ref "R36") (pin "2") (pinfunction "2_2") (pintype "passive"))
    )
    (net (code "88") (name "Net-(AD20-PadA)") (class "Default")
      (node (ref "AD20") (pin "A") (pinfunction "A_A") (pintype "passive"))
      (node (ref "R37") (pin "2") (pinfunction "2_2") (pintype "passive"))
    )
    (net (code "89") (name "Net-(AD21-PadA)") (class "Default")
      (node (ref "AD21") (pin "A") (pinfunction "A_A") (pintype "passive"))
      (node (ref "R38") (pin "2") (pinfunction "2_2") (pintype "passive"))
    )
    (net (code "90") (name "Net-(AD22-PadA)") (class "Default")
      (node (ref "AD22") (pin "A") (pinfunction "A_A") (pintype "passive"))
      (node (ref "R39") (pin "2") (pinfunction "2_2") (pintype "passive"))
    )
    (net (code "91") (name "Net-(AD23-PadA)") (class "Default")
      (node (ref "AD23") (pin "A") (pinfunction "A_A") (pintype "passive"))
      (node (ref "R40") (pin "2") (pinfunction "2_2") (pintype "passive"))
    )
    (net (code "92") (name "Net-(AUX0-PadA)") (class "Default")
      (node (ref "AUX0") (pin "A") (pinfunction "A_A") (pintype "passive"))
      (node (ref "R49") (pin "2") (pinfunction "2_2") (pintype "passive"))
    )
    (net (code "93") (name "Net-(AUX1-PadA)") (class "Default")
      (node (ref "AUX1") (pin "A") (pinfunction "A_A") (pintype "passive"))
      (node (ref "R50") (pin "2") (pinfunction "2_2") (pintype "passive"))
    )
    (net (code "94") (name "Net-(AUX2-PadA)") (class "Default")
      (node (ref "AUX2") (pin "A") (pinfunction "A_A") (pintype "passive"))
      (node (ref "R51") (pin "2") (pinfunction "2_2") (pintype "passive"))
    )
    (net (code "95") (name "Net-(AUX3-PadA)") (class "Default")
      (node (ref "AUX3") (pin "A") (pinfunction "A_A") (pintype "passive"))
      (node (ref "R52") (pin "2") (pinfunction "2_2") (pintype "passive"))
    )
    (net (code "96") (name "Net-(AUX4-PadA)") (class "Default")
      (node (ref "AUX4") (pin "A") (pinfunction "A_A") (pintype "passive"))
      (node (ref "R53") (pin "2") (pinfunction "2_2") (pintype "passive"))
    )
    (net (code "97") (name "Net-(AUX5-PadA)") (class "Default")
      (node (ref "AUX5") (pin "A") (pinfunction "A_A") (pintype "passive"))
      (node (ref "R54") (pin "2") (pinfunction "2_2") (pintype "passive"))
    )
    (net (code "98") (name "Net-(AUX6-PadA)") (class "Default")
      (node (ref "AUX6") (pin "A") (pinfunction "A_A") (pintype "passive"))
      (node (ref "R55") (pin "2") (pinfunction "2_2") (pintype "passive"))
    )
    (net (code "99") (name "Net-(AUX7-PadA)") (class "Default")
      (node (ref "AUX7") (pin "A") (pinfunction "A_A") (pintype "passive"))
      (node (ref "R56") (pin "2") (pinfunction "2_2") (pintype "passive"))
    )
    (net (code "100") (name "Net-(DAT0-PadA)") (class "Default")
      (node (ref "DAT0") (pin "A") (pinfunction "A_A") (pintype "passive"))
      (node (ref "R9") (pin "2") (pinfunction "2_2") (pintype "passive"))
    )
    (net (code "101") (name "Net-(DAT1-PadA)") (class "Default")
      (node (ref "DAT1") (pin "A") (pinfunction "A_A") (pintype "passive"))
      (node (ref "R10") (pin "2") (pinfunction "2_2") (pintype "passive"))
    )
    (net (code "102") (name "Net-(DAT2-PadA)") (class "Default")
      (node (ref "DAT2") (pin "A") (pinfunction "A_A") (pintype "passive"))
      (node (ref "R11") (pin "2") (pinfunction "2_2") (pintype "passive"))
    )
    (net (code "103") (name "Net-(DAT3-PadA)") (class "Default")
      (node (ref "DAT3") (pin "A") (pinfunction "A_A") (pintype "passive"))
      (node (ref "R12") (pin "2") (pinfunction "2_2") (pintype "passive"))
    )
    (net (code "104") (name "Net-(DAT4-PadA)") (class "Default")
      (node (ref "DAT4") (pin "A") (pinfunction "A_A") (pintype "passive"))
      (node (ref "R13") (pin "2") (pinfunction "2_2") (pintype "passive"))
    )
    (net (code "105") (name "Net-(DAT5-PadA)") (class "Default")
      (node (ref "DAT5") (pin "A") (pinfunction "A_A") (pintype "passive"))
      (node (ref "R14") (pin "2") (pinfunction "2_2") (pintype "passive"))
    )
    (net (code "106") (name "Net-(DAT6-PadA)") (class "Default")
      (node (ref "DAT6") (pin "A") (pinfunction "A_A") (pintype "passive"))
      (node (ref "R15") (pin "2") (pinfunction "2_2") (pintype "passive"))
    )
    (net (code "107") (name "Net-(DAT7-PadA)") (class "Default")
      (node (ref "DAT7") (pin "A") (pinfunction "A_A") (pintype "passive"))
      (node (ref "R16") (pin "2") (pinfunction "2_2") (pintype "passive"))
    )
    (net (code "108") (name "Net-(ICSP-Pad1)") (class "Default")
      (node (ref "ICSP") (pin "1") (pinfunction "1_1") (pintype "passive"))
      (node (ref "M1") (pin "D12") (pinfunction "D12_D12") (pintype "bidirectional"))
    )
    (net (code "109") (name "Net-(ICSP-Pad3)") (class "Default")
      (node (ref "ICSP") (pin "3") (pinfunction "3_3") (pintype "passive"))
      (node (ref "M1") (pin "D13") (pinfunction "D13_D13") (pintype "bidirectional"))
    )
    (net (code "110") (name "Net-(ICSP-Pad4)") (class "Default")
      (node (ref "ICSP") (pin "4") (pinfunction "4_4") (pintype "passive"))
      (node (ref "M1") (pin "D11") (pinfunction "D11_D11") (pintype "bidirectional"))
    )
    (net (code "111") (name "Net-(R1-Pad1)") (class "Default")
      (node (ref "R1") (pin "1") (pinfunction "1_1") (pintype "passive"))
      (node (ref "SLOT7") (pin "B9") (pinfunction "B9_B9") (pintype "bidirectional"))
    )
    (net (code "112") (name "Net-(R2-Pad1)") (class "Default")
      (node (ref "R2") (pin "1") (pinfunction "1_1") (pintype "passive"))
      (node (ref "SLOT6") (pin "B9") (pinfunction "B9_B9") (pintype "bidirectional"))
    )
    (net (code "113") (name "Net-(R3-Pad1)") (class "Default")
      (node (ref "R3") (pin "1") (pinfunction "1_1") (pintype "passive"))
      (node (ref "SLOT5") (pin "B9") (pinfunction "B9_B9") (pintype "bidirectional"))
    )
    (net (code "114") (name "Net-(R4-Pad1)") (class "Default")
      (node (ref "R4") (pin "1") (pinfunction "1_1") (pintype "passive"))
      (node (ref "SLOT4") (pin "B9") (pinfunction "B9_B9") (pintype "bidirectional"))
    )
    (net (code "115") (name "Net-(R5-Pad1)") (class "Default")
      (node (ref "R5") (pin "1") (pinfunction "1_1") (pintype "passive"))
      (node (ref "SLOT3") (pin "B9") (pinfunction "B9_B9") (pintype "bidirectional"))
    )
    (net (code "116") (name "Net-(R6-Pad1)") (class "Default")
      (node (ref "R6") (pin "1") (pinfunction "1_1") (pintype "passive"))
      (node (ref "SLOT2") (pin "B9") (pinfunction "B9_B9") (pintype "bidirectional"))
    )
    (net (code "117") (name "Net-(R7-Pad1)") (class "Default")
      (node (ref "R7") (pin "1") (pinfunction "1_1") (pintype "passive"))
      (node (ref "SLOT1") (pin "B9") (pinfunction "B9_B9") (pintype "bidirectional"))
    )
    (net (code "118") (name "Net-(R8-Pad1)") (class "Default")
      (node (ref "R8") (pin "1") (pinfunction "1_1") (pintype "passive"))
      (node (ref "SLOT0") (pin "B9") (pinfunction "B9_B9") (pintype "bidirectional"))
    )
    (net (code "119") (name "Net-(R41-Pad2)") (class "Default")
      (node (ref "R41") (pin "2") (pinfunction "2_2") (pintype "passive"))
      (node (ref "WAIT") (pin "A") (pinfunction "A_A") (pintype "passive"))
    )
    (net (code "120") (name "Net-(RGB0-IN)") (class "Default")
      (node (ref "R62") (pin "2") (pinfunction "2_2") (pintype "passive"))
      (node (ref "RGB0") (pin "1") (pinfunction "IN_1") (pintype "bidirectional"))
    )
    (net (code "121") (name "Net-(RGB0-OUT)") (class "Default")
      (node (ref "RGB0") (pin "3") (pinfunction "OUT_3") (pintype "bidirectional"))
      (node (ref "RGB1") (pin "1") (pinfunction "IN_1") (pintype "bidirectional"))
    )
    (net (code "122") (name "Net-(RGB1-OUT)") (class "Default")
      (node (ref "RGB1") (pin "3") (pinfunction "OUT_3") (pintype "bidirectional"))
      (node (ref "RGB2") (pin "1") (pinfunction "IN_1") (pintype "bidirectional"))
    )
    (net (code "123") (name "Net-(RGB2-OUT)") (class "Default")
      (node (ref "RGB2") (pin "3") (pinfunction "OUT_3") (pintype "bidirectional"))
      (node (ref "RGB3") (pin "1") (pinfunction "IN_1") (pintype "bidirectional"))
    )
    (net (code "124") (name "Net-(RGB3-OUT)") (class "Default")
      (node (ref "RGB3") (pin "3") (pinfunction "OUT_3") (pintype "bidirectional"))
      (node (ref "RGB4") (pin "1") (pinfunction "IN_1") (pintype "bidirectional"))
    )
    (net (code "125") (name "Net-(RGB4-OUT)") (class "Default")
      (node (ref "RGB4") (pin "3") (pinfunction "OUT_3") (pintype "bidirectional"))
      (node (ref "RGB5") (pin "1") (pinfunction "IN_1") (pintype "bidirectional"))
    )
    (net (code "126") (name "Net-(RGB5-OUT)") (class "Default")
      (node (ref "RGB5") (pin "3") (pinfunction "OUT_3") (pintype "bidirectional"))
      (node (ref "RGB6") (pin "1") (pinfunction "IN_1") (pintype "bidirectional"))
    )
    (net (code "127") (name "Net-(RGB6-OUT)") (class "Default")
      (node (ref "RGB6") (pin "3") (pinfunction "OUT_3") (pintype "bidirectional"))
      (node (ref "RGB7") (pin "1") (pinfunction "IN_1") (pintype "bidirectional"))
    )
    (net (code "128") (name "Net-(RGB7-OUT)") (class "Default")
      (node (ref "RGB7") (pin "3") (pinfunction "OUT_3") (pintype "bidirectional"))
      (node (ref "RGB8") (pin "1") (pinfunction "IN_1") (pintype "bidirectional"))
    )
    (net (code "129") (name "Net-(RGB8-OUT)") (class "Default")
      (node (ref "RGB8") (pin "3") (pinfunction "OUT_3") (pintype "bidirectional"))
      (node (ref "RGB9") (pin "1") (pinfunction "IN_1") (pintype "bidirectional"))
    )
    (net (code "130") (name "Net-(RGB10-IN)") (class "Default")
      (node (ref "RGB10") (pin "1") (pinfunction "IN_1") (pintype "bidirectional"))
      (node (ref "RGB9") (pin "3") (pinfunction "OUT_3") (pintype "bidirectional"))
    )
    (net (code "131") (name "Net-(RGB10-OUT)") (class "Default")
      (node (ref "RGB10") (pin "3") (pinfunction "OUT_3") (pintype "bidirectional"))
      (node (ref "RGB11") (pin "1") (pinfunction "IN_1") (pintype "bidirectional"))
    )
    (net (code "132") (name "Net-(RGB11-OUT)") (class "Default")
      (node (ref "RGB11") (pin "3") (pinfunction "OUT_3") (pintype "bidirectional"))
      (node (ref "RGB12") (pin "1") (pinfunction "IN_1") (pintype "bidirectional"))
    )
    (net (code "133") (name "Net-(RGB12-OUT)") (class "Default")
      (node (ref "RGB12") (pin "3") (pinfunction "OUT_3") (pintype "bidirectional"))
      (node (ref "RGB13") (pin "1") (pinfunction "IN_1") (pintype "bidirectional"))
    )
    (net (code "134") (name "VCC") (class "Default")
      (node (ref "C1") (pin "1") (pinfunction "1_1") (pintype "passive"))
      (node (ref "C10") (pin "1") (pinfunction "1_1") (pintype "passive"))
      (node (ref "C11") (pin "1") (pinfunction "1_1") (pintype "passive"))
      (node (ref "C12") (pin "1") (pinfunction "1_1") (pintype "passive"))
      (node (ref "C13") (pin "1") (pinfunction "1_1") (pintype "passive"))
      (node (ref "C14") (pin "1") (pinfunction "1_1") (pintype "passive"))
      (node (ref "C2") (pin "1") (pinfunction "1_1") (pintype "passive"))
      (node (ref "C3") (pin "1") (pinfunction "1_1") (pintype "passive"))
      (node (ref "C4") (pin "1") (pinfunction "1_1") (pintype "passive"))
      (node (ref "C5") (pin "1") (pinfunction "1_1") (pintype "passive"))
      (node (ref "C6") (pin "1") (pinfunction "1_1") (pintype "passive"))
      (node (ref "C7") (pin "1") (pinfunction "1_1") (pintype "passive"))
      (node (ref "C8") (pin "1") (pinfunction "1_1") (pintype "passive"))
      (node (ref "C9") (pin "1") (pinfunction "1_1") (pintype "passive"))
      (node (ref "ICSP") (pin "2") (pinfunction "2_2") (pintype "passive"))
      (node (ref "J15") (pin "4") (pinfunction "4_4") (pintype "passive"))
      (node (ref "M1") (pin "VCC") (pinfunction "VCC_VCC") (pintype "bidirectional"))
      (node (ref "P_SW") (pin "1") (pinfunction "1_1") (pintype "passive"))
      (node (ref "R59") (pin "2") (pinfunction "2_2") (pintype "passive"))
      (node (ref "R60") (pin "2") (pinfunction "2_2") (pintype "passive"))
      (node (ref "R61") (pin "2") (pinfunction "2_2") (pintype "passive"))
      (node (ref "RGB0") (pin "2") (pinfunction "VDD_2") (pintype "bidirectional"))
      (node (ref "RGB1") (pin "2") (pinfunction "VDD_2") (pintype "bidirectional"))
      (node (ref "RGB10") (pin "2") (pinfunction "VDD_2") (pintype "bidirectional"))
      (node (ref "RGB11") (pin "2") (pinfunction "VDD_2") (pintype "bidirectional"))
      (node (ref "RGB12") (pin "2") (pinfunction "VDD_2") (pintype "bidirectional"))
      (node (ref "RGB13") (pin "2") (pinfunction "VDD_2") (pintype "bidirectional"))
      (node (ref "RGB2") (pin "2") (pinfunction "VDD_2") (pintype "bidirectional"))
      (node (ref "RGB3") (pin "2") (pinfunction "VDD_2") (pintype "bidirectional"))
      (node (ref "RGB4") (pin "2") (pinfunction "VDD_2") (pintype "bidirectional"))
      (node (ref "RGB5") (pin "2") (pinfunction "VDD_2") (pintype "bidirectional"))
      (node (ref "RGB6") (pin "2") (pinfunction "VDD_2") (pintype "bidirectional"))
      (node (ref "RGB7") (pin "2") (pinfunction "VDD_2") (pintype "bidirectional"))
      (node (ref "RGB8") (pin "2") (pinfunction "VDD_2") (pintype "bidirectional"))
      (node (ref "RGB9") (pin "2") (pinfunction "VDD_2") (pintype "bidirectional"))
      (node (ref "SLOT0") (pin "A6") (pinfunction "A6_A6") (pintype "bidirectional"))
      (node (ref "SLOT0") (pin "A7") (pinfunction "A7_A7") (pintype "bidirectional"))
      (node (ref "SLOT0") (pin "B6") (pinfunction "B6_B6") (pintype "bidirectional"))
      (node (ref "SLOT0") (pin "B7") (pinfunction "B7_B7") (pintype "bidirectional"))
      (node (ref "SLOT1") (pin "A6") (pinfunction "A6_A6") (pintype "bidirectional"))
      (node (ref "SLOT1") (pin "A7") (pinfunction "A7_A7") (pintype "bidirectional"))
      (node (ref "SLOT1") (pin "B6") (pinfunction "B6_B6") (pintype "bidirectional"))
      (node (ref "SLOT1") (pin "B7") (pinfunction "B7_B7") (pintype "bidirectional"))
      (node (ref "SLOT2") (pin "A6") (pinfunction "A6_A6") (pintype "bidirectional"))
      (node (ref "SLOT2") (pin "A7") (pinfunction "A7_A7") (pintype "bidirectional"))
      (node (ref "SLOT2") (pin "B6") (pinfunction "B6_B6") (pintype "bidirectional"))
      (node (ref "SLOT2") (pin "B7") (pinfunction "B7_B7") (pintype "bidirectional"))
      (node (ref "SLOT3") (pin "A6") (pinfunction "A6_A6") (pintype "bidirectional"))
      (node (ref "SLOT3") (pin "A7") (pinfunction "A7_A7") (pintype "bidirectional"))
      (node (ref "SLOT3") (pin "B6") (pinfunction "B6_B6") (pintype "bidirectional"))
      (node (ref "SLOT3") (pin "B7") (pinfunction "B7_B7") (pintype "bidirectional"))
      (node (ref "SLOT4") (pin "A6") (pinfunction "A6_A6") (pintype "bidirectional"))
      (node (ref "SLOT4") (pin "A7") (pinfunction "A7_A7") (pintype "bidirectional"))
      (node (ref "SLOT4") (pin "B6") (pinfunction "B6_B6") (pintype "bidirectional"))
      (node (ref "SLOT4") (pin "B7") (pinfunction "B7_B7") (pintype "bidirectional"))
      (node (ref "SLOT5") (pin "A6") (pinfunction "A6_A6") (pintype "bidirectional"))
      (node (ref "SLOT5") (pin "A7") (pinfunction "A7_A7") (pintype "bidirectional"))
      (node (ref "SLOT5") (pin "B6") (pinfunction "B6_B6") (pintype "bidirectional"))
      (node (ref "SLOT5") (pin "B7") (pinfunction "B7_B7") (pintype "bidirectional"))
      (node (ref "SLOT6") (pin "A6") (pinfunction "A6_A6") (pintype "bidirectional"))
      (node (ref "SLOT6") (pin "A7") (pinfunction "A7_A7") (pintype "bidirectional"))
      (node (ref "SLOT6") (pin "B6") (pinfunction "B6_B6") (pintype "bidirectional"))
      (node (ref "SLOT6") (pin "B7") (pinfunction "B7_B7") (pintype "bidirectional"))
      (node (ref "SLOT7") (pin "A6") (pinfunction "A6_A6") (pintype "bidirectional"))
      (node (ref "SLOT7") (pin "A7") (pinfunction "A7_A7") (pintype "bidirectional"))
      (node (ref "SLOT7") (pin "B6") (pinfunction "B6_B6") (pintype "bidirectional"))
      (node (ref "SLOT7") (pin "B7") (pinfunction "B7_B7") (pintype "bidirectional"))
      (node (ref "U1") (pin "3") (pinfunction "VCC_3") (pintype "power_in"))
    )
    (net (code "135") (name "unconnected-(M1-PadA0)") (class "Default")
      (node (ref "M1") (pin "A0") (pinfunction "A0_A0") (pintype "bidirectional"))
    )
    (net (code "136") (name "unconnected-(M1-PadA1)") (class "Default")
      (node (ref "M1") (pin "A1") (pinfunction "A1_A1") (pintype "bidirectional"))
    )
    (net (code "137") (name "unconnected-(M1-PadA2)") (class "Default")
      (node (ref "M1") (pin "A2") (pinfunction "A2_A2") (pintype "bidirectional"))
    )
    (net (code "138") (name "unconnected-(M1-PadA3)") (class "Default")
      (node (ref "M1") (pin "A3") (pinfunction "A3_A3") (pintype "bidirectional"))
    )
    (net (code "139") (name "unconnected-(M1-PadA6)") (class "Default")
      (node (ref "M1") (pin "A6") (pinfunction "A6_A6") (pintype "bidirectional"))
    )
    (net (code "140") (name "unconnected-(M1-PadA7)") (class "Default")
      (node (ref "M1") (pin "A7") (pinfunction "A7_A7") (pintype "bidirectional"))
    )
    (net (code "141") (name "unconnected-(M1-PadAREF)") (class "Default")
      (node (ref "M1") (pin "AREF") (pinfunction "AREF_AREF") (pintype "bidirectional"))
    )
    (net (code "142") (name "unconnected-(M1-PadD2)") (class "Default")
      (node (ref "M1") (pin "D2") (pinfunction "D2_D2") (pintype "bidirectional"))
    )
    (net (code "143") (name "unconnected-(M1-PadD3)") (class "Default")
      (node (ref "M1") (pin "D3") (pinfunction "D3_D3") (pintype "bidirectional"))
    )
    (net (code "144") (name "unconnected-(M1-PadD4)") (class "Default")
      (node (ref "M1") (pin "D4") (pinfunction "D4_D4") (pintype "bidirectional"))
    )
    (net (code "145") (name "unconnected-(M1-PadD5)") (class "Default")
      (node (ref "M1") (pin "D5") (pinfunction "D5_D5") (pintype "bidirectional"))
    )
    (net (code "146") (name "unconnected-(M1-PadD6)") (class "Default")
      (node (ref "M1") (pin "D6") (pinfunction "D6_D6") (pintype "bidirectional"))
    )
    (net (code "147") (name "unconnected-(M1-PadD8)") (class "Default")
      (node (ref "M1") (pin "D8") (pinfunction "D8_D8") (pintype "bidirectional"))
    )
    (net (code "148") (name "unconnected-(M1-PadD9)") (class "Default")
      (node (ref "M1") (pin "D9") (pinfunction "D9_D9") (pintype "bidirectional"))
    )
    (net (code "149") (name "unconnected-(M1-PadD10)") (class "Default")
      (node (ref "M1") (pin "D10") (pinfunction "D10_D10") (pintype "bidirectional"))
    )
    (net (code "150") (name "unconnected-(RGB13-OUT-Pad3)") (class "Default")
      (node (ref "RGB13") (pin "3") (pinfunction "OUT_3") (pintype "bidirectional"))
    )
  )
)
